# Digitalizador_RPi_Copia_en_conflicto_de_.net
KiCad netlist of a schematic drawn in Altium Designer
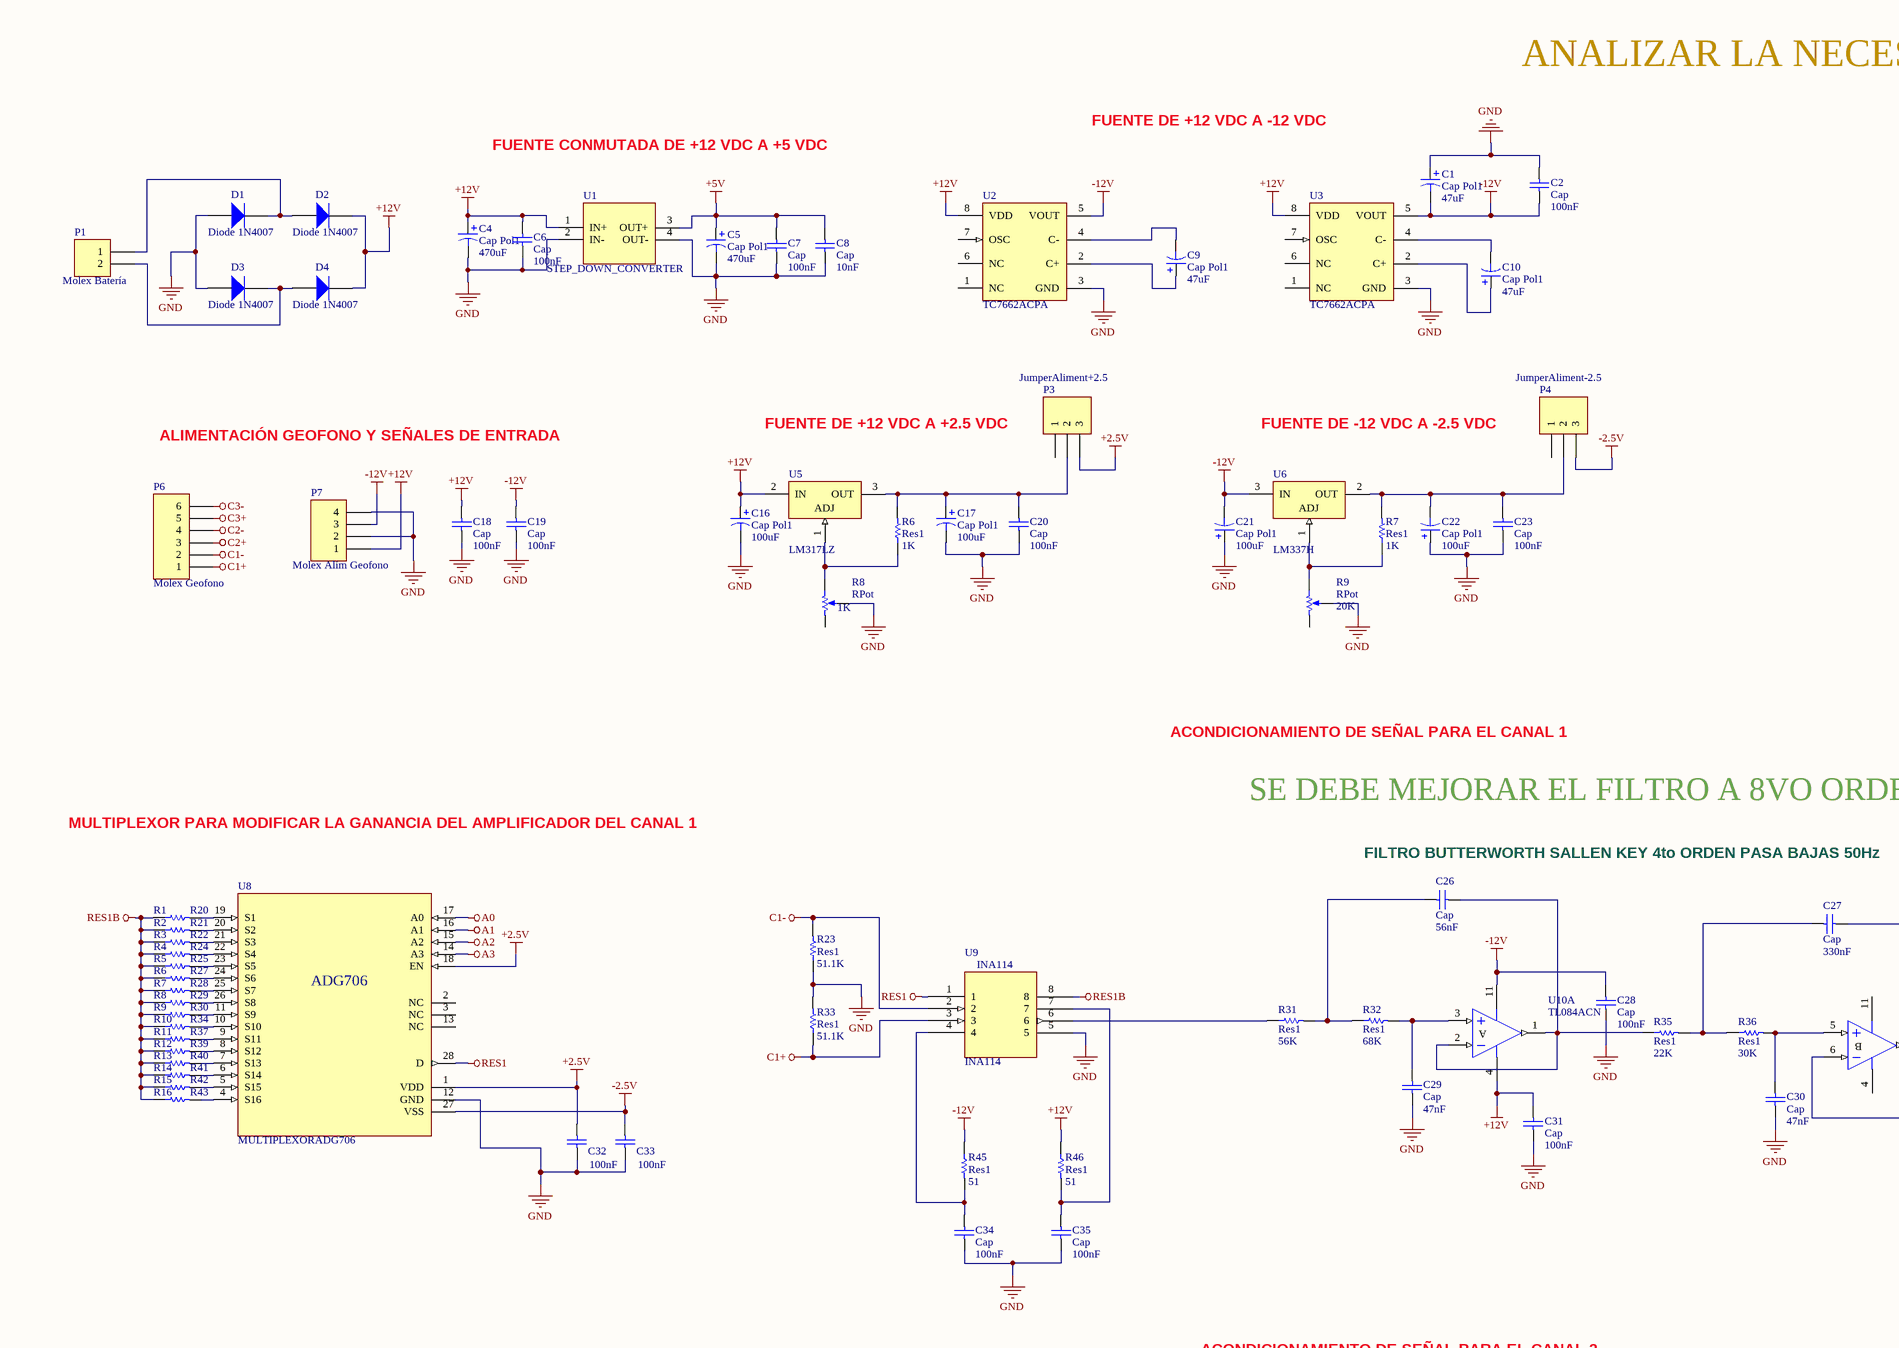
[diagram p0: Digitalizador_RPi (Copia en conflicto de Ivan Palacios 2020-06-25).SchDoc, top left]
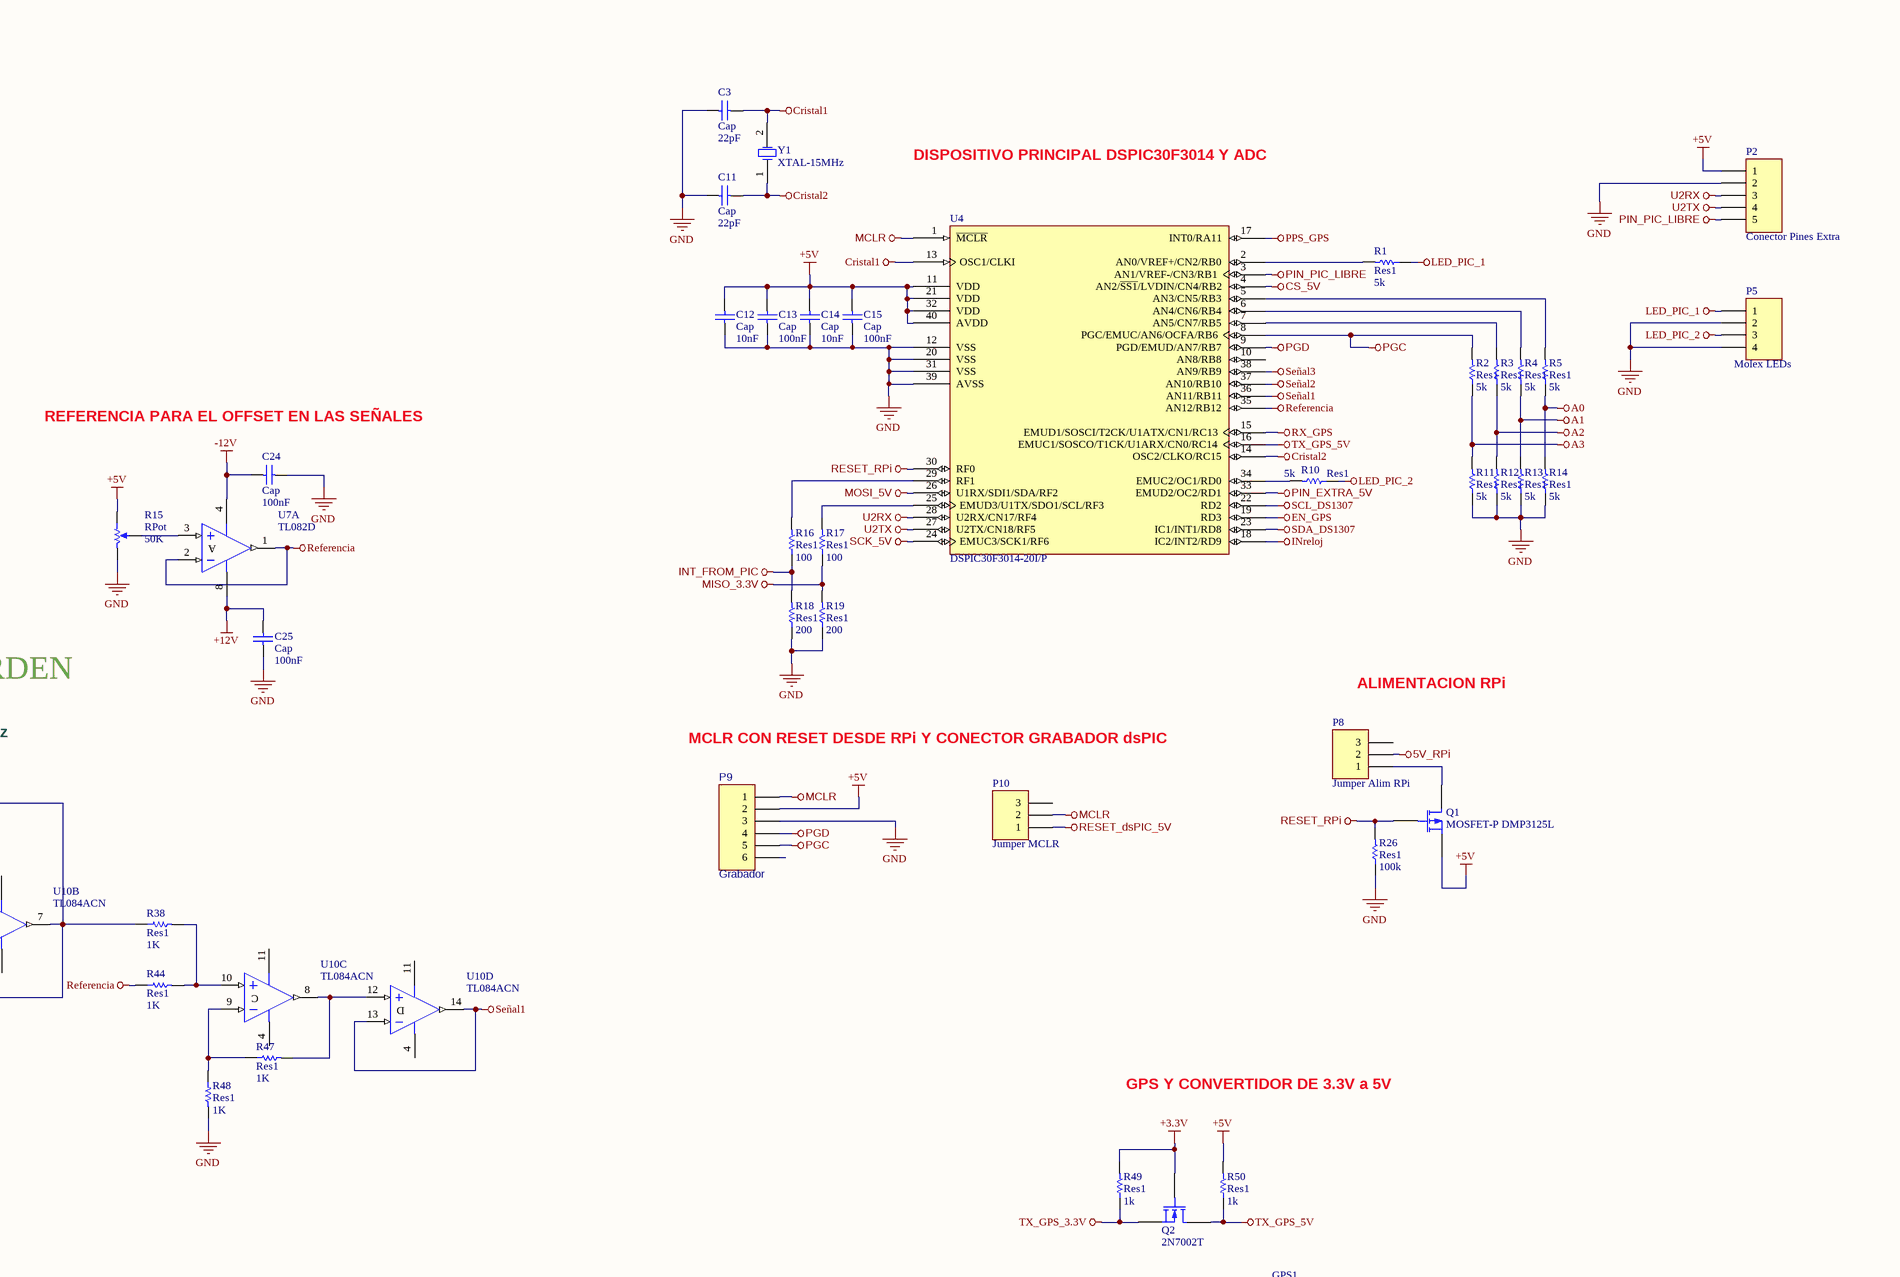
[diagram p1: Digitalizador_RPi (Copia en conflicto de Ivan Palacios 2020-06-25).SchDoc, top right]
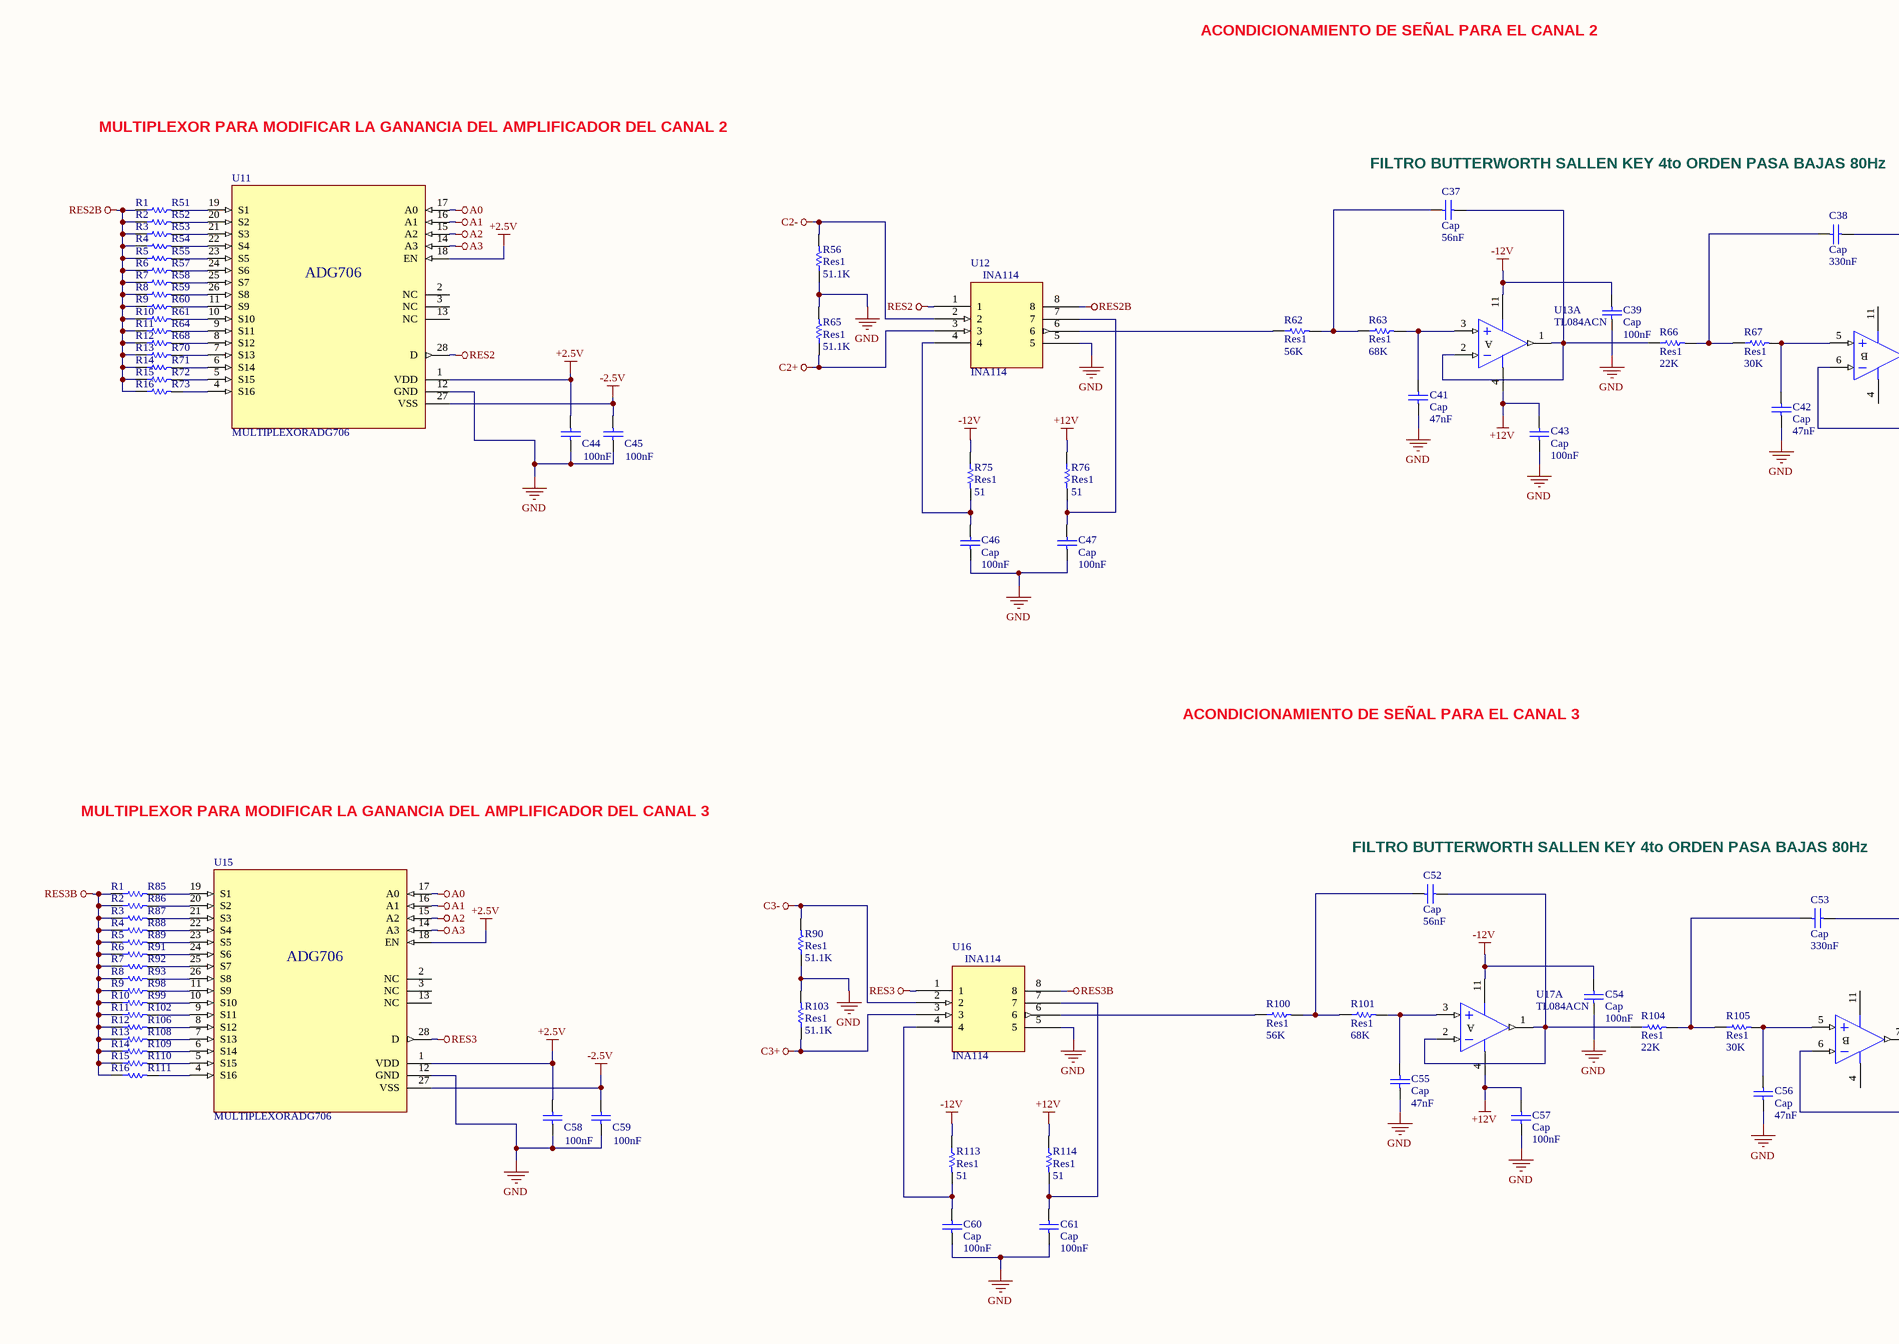
[diagram p2: Digitalizador_RPi (Copia en conflicto de Ivan Palacios 2020-06-25).SchDoc, bottom left]
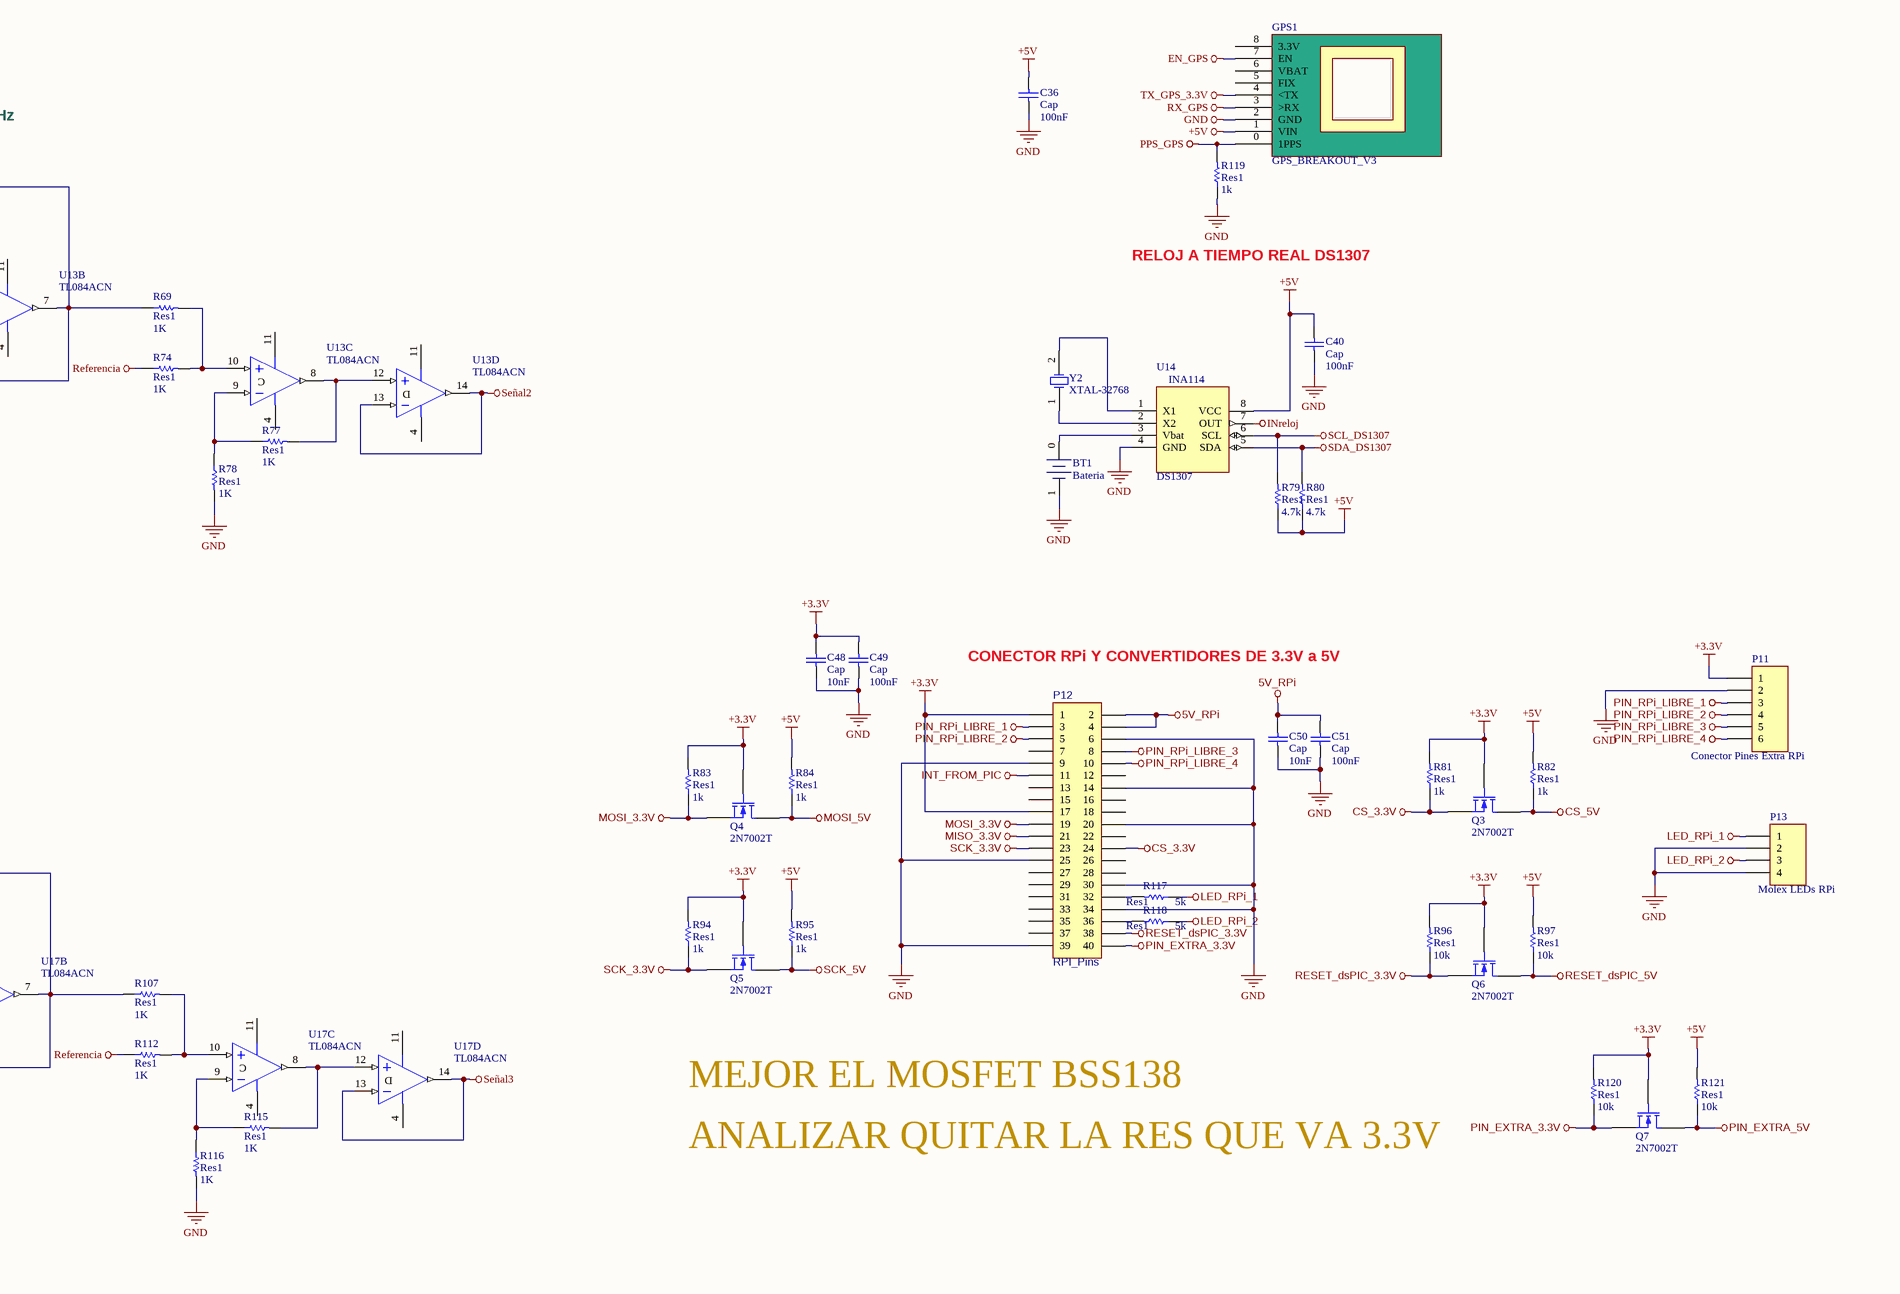
[diagram p3: Digitalizador_RPi (Copia en conflicto de Ivan Palacios 2020-06-25).SchDoc, bottom right]

(export (version "E")
  (design (tool "Eeschema 10.0.6"))
  (components
    (comp (ref "BT1")
      (value "Bateria")
      (footprint "Bateria-DS1307")
      (libsource (lib "Libreria RSA") (part "BateriaDS1307"))
    )
    (comp (ref "C1")
      (value "Cap Pol1")
      (footprint "CAP_5.5MM")
      (description "Polarized Capacitor (Radial)")
      (fields (field (name "ALTIUM_VALUE") "47uF") (field (name "PUBLISHER") "Altium Limited"))
      (libsource (lib "Miscellaneous Devices") (part "Cap Pol1"))
    )
    (comp (ref "C2")
      (value "Cap")
      (footprint "0603")
      (description "Capacitor")
      (fields (field (name "ALTIUM_VALUE") "100nF") (field (name "PUBLISHER") "Altium Limited"))
      (libsource (lib "Miscellaneous Devices") (part "Cap"))
    )
    (comp (ref "C3")
      (value "Cap")
      (footprint "0603")
      (description "Capacitor")
      (fields (field (name "ALTIUM_VALUE") "22pF") (field (name "PUBLISHER") "Altium Limited"))
      (libsource (lib "Miscellaneous Devices") (part "Cap"))
    )
    (comp (ref "C4")
      (value "Cap Pol1")
      (footprint "CAP_8.5mm")
      (description "Polarized Capacitor (Radial)")
      (fields (field (name "ALTIUM_VALUE") "470uF") (field (name "PUBLISHER") "Altium Limited"))
      (libsource (lib "Miscellaneous Devices") (part "Cap Pol1"))
    )
    (comp (ref "C5")
      (value "Cap Pol1")
      (footprint "CAP_8.5mm")
      (description "Polarized Capacitor (Radial)")
      (fields (field (name "ALTIUM_VALUE") "470uF") (field (name "PUBLISHER") "Altium Limited"))
      (libsource (lib "Miscellaneous Devices") (part "Cap Pol1"))
    )
    (comp (ref "C6")
      (value "Cap")
      (footprint "0603")
      (description "Capacitor")
      (fields (field (name "ALTIUM_VALUE") "100nF") (field (name "PUBLISHER") "Altium Limited"))
      (libsource (lib "Miscellaneous Devices") (part "Cap"))
    )
    (comp (ref "C7")
      (value "Cap")
      (footprint "0603")
      (description "Capacitor")
      (fields (field (name "ALTIUM_VALUE") "100nF") (field (name "PUBLISHER") "Altium Limited"))
      (libsource (lib "Miscellaneous Devices") (part "Cap"))
    )
    (comp (ref "C8")
      (value "Cap")
      (footprint "0603")
      (description "Capacitor")
      (fields (field (name "ALTIUM_VALUE") "10nF") (field (name "PUBLISHER") "Altium Limited"))
      (libsource (lib "Miscellaneous Devices") (part "Cap"))
    )
    (comp (ref "C9")
      (value "Cap Pol1")
      (footprint "CAP_5.5MM")
      (description "Polarized Capacitor (Radial)")
      (fields (field (name "ALTIUM_VALUE") "47uF") (field (name "PUBLISHER") "Altium Limited"))
      (libsource (lib "Miscellaneous Devices") (part "Cap Pol1"))
    )
    (comp (ref "C10")
      (value "Cap Pol1")
      (footprint "CAP_5.5MM")
      (description "Polarized Capacitor (Radial)")
      (fields (field (name "ALTIUM_VALUE") "47uF") (field (name "PUBLISHER") "Altium Limited"))
      (libsource (lib "Miscellaneous Devices") (part "Cap Pol1"))
    )
    (comp (ref "C11")
      (value "Cap")
      (footprint "0603")
      (description "Capacitor")
      (fields (field (name "ALTIUM_VALUE") "22pF") (field (name "PUBLISHER") "Altium Limited"))
      (libsource (lib "Miscellaneous Devices") (part "Cap"))
    )
    (comp (ref "C12")
      (value "Cap")
      (footprint "0603")
      (description "Capacitor")
      (fields (field (name "ALTIUM_VALUE") "10nF") (field (name "PUBLISHER") "Altium Limited"))
      (libsource (lib "Miscellaneous Devices") (part "Cap"))
    )
    (comp (ref "C13")
      (value "Cap")
      (footprint "0603")
      (description "Capacitor")
      (fields (field (name "ALTIUM_VALUE") "100nF") (field (name "PUBLISHER") "Altium Limited"))
      (libsource (lib "Miscellaneous Devices") (part "Cap"))
    )
    (comp (ref "C14")
      (value "Cap")
      (footprint "0603")
      (description "Capacitor")
      (fields (field (name "ALTIUM_VALUE") "10nF") (field (name "PUBLISHER") "Altium Limited"))
      (libsource (lib "Miscellaneous Devices") (part "Cap"))
    )
    (comp (ref "C15")
      (value "Cap")
      (footprint "0603")
      (description "Capacitor")
      (fields (field (name "ALTIUM_VALUE") "100nF") (field (name "PUBLISHER") "Altium Limited"))
      (libsource (lib "Miscellaneous Devices") (part "Cap"))
    )
    (comp (ref "C16")
      (value "Cap Pol1")
      (footprint "CAP_5.5MM")
      (description "Polarized Capacitor (Radial)")
      (fields (field (name "ALTIUM_VALUE") "100uF") (field (name "PUBLISHER") "Altium Limited"))
      (libsource (lib "Miscellaneous Devices") (part "Cap Pol1"))
    )
    (comp (ref "C17")
      (value "Cap Pol1")
      (footprint "CAP_5.5MM")
      (description "Polarized Capacitor (Radial)")
      (fields (field (name "ALTIUM_VALUE") "100uF") (field (name "PUBLISHER") "Altium Limited"))
      (libsource (lib "Miscellaneous Devices") (part "Cap Pol1"))
    )
    (comp (ref "C18")
      (value "Cap")
      (footprint "0603")
      (description "Capacitor")
      (fields (field (name "ALTIUM_VALUE") "100nF") (field (name "PUBLISHER") "Altium Limited"))
      (libsource (lib "Miscellaneous Devices") (part "Cap"))
    )
    (comp (ref "C19")
      (value "Cap")
      (footprint "0603")
      (description "Capacitor")
      (fields (field (name "ALTIUM_VALUE") "100nF") (field (name "PUBLISHER") "Altium Limited"))
      (libsource (lib "Miscellaneous Devices") (part "Cap"))
    )
    (comp (ref "C20")
      (value "Cap")
      (footprint "0603")
      (description "Capacitor")
      (fields (field (name "ALTIUM_VALUE") "100nF") (field (name "PUBLISHER") "Altium Limited"))
      (libsource (lib "Miscellaneous Devices") (part "Cap"))
    )
    (comp (ref "C21")
      (value "Cap Pol1")
      (footprint "CAP_5.5MM")
      (description "Polarized Capacitor (Radial)")
      (fields (field (name "ALTIUM_VALUE") "100uF") (field (name "PUBLISHER") "Altium Limited"))
      (libsource (lib "Miscellaneous Devices") (part "Cap Pol1"))
    )
    (comp (ref "C22")
      (value "Cap Pol1")
      (footprint "CAP_5.5MM")
      (description "Polarized Capacitor (Radial)")
      (fields (field (name "ALTIUM_VALUE") "100uF") (field (name "PUBLISHER") "Altium Limited"))
      (libsource (lib "Miscellaneous Devices") (part "Cap Pol1"))
    )
    (comp (ref "C23")
      (value "Cap")
      (footprint "0603")
      (description "Capacitor")
      (fields (field (name "ALTIUM_VALUE") "100nF") (field (name "PUBLISHER") "Altium Limited"))
      (libsource (lib "Miscellaneous Devices") (part "Cap"))
    )
    (comp (ref "C24")
      (value "Cap")
      (footprint "0603")
      (description "Capacitor")
      (fields (field (name "ALTIUM_VALUE") "100nF") (field (name "PUBLISHER") "Altium Limited"))
      (libsource (lib "Miscellaneous Devices") (part "Cap"))
    )
    (comp (ref "C25")
      (value "Cap")
      (footprint "0603")
      (description "Capacitor")
      (fields (field (name "ALTIUM_VALUE") "100nF") (field (name "PUBLISHER") "Altium Limited"))
      (libsource (lib "Miscellaneous Devices") (part "Cap"))
    )
    (comp (ref "C26")
      (value "Cap")
      (footprint "RAD0.2")
      (description "Capacitor")
      (fields (field (name "ALTIUM_VALUE") "56nF") (field (name "PUBLISHER") "Altium Limited"))
      (libsource (lib "Miscellaneous Devices") (part "Cap"))
    )
    (comp (ref "C27")
      (value "Cap")
      (footprint "RAD0.2")
      (description "Capacitor")
      (fields (field (name "ALTIUM_VALUE") "330nF") (field (name "PUBLISHER") "Altium Limited"))
      (libsource (lib "Miscellaneous Devices") (part "Cap"))
    )
    (comp (ref "C28")
      (value "Cap")
      (footprint "0603")
      (description "Capacitor")
      (fields (field (name "ALTIUM_VALUE") "100nF") (field (name "PUBLISHER") "Altium Limited"))
      (libsource (lib "Miscellaneous Devices") (part "Cap"))
    )
    (comp (ref "C29")
      (value "Cap")
      (footprint "RAD0.2")
      (description "Capacitor")
      (fields (field (name "ALTIUM_VALUE") "47nF") (field (name "PUBLISHER") "Altium Limited"))
      (libsource (lib "Miscellaneous Devices") (part "Cap"))
    )
    (comp (ref "C30")
      (value "Cap")
      (footprint "RAD0.2")
      (description "Capacitor")
      (fields (field (name "ALTIUM_VALUE") "47nF") (field (name "PUBLISHER") "Altium Limited"))
      (libsource (lib "Miscellaneous Devices") (part "Cap"))
    )
    (comp (ref "C31")
      (value "Cap")
      (footprint "0603")
      (description "Capacitor")
      (fields (field (name "ALTIUM_VALUE") "100nF") (field (name "PUBLISHER") "Altium Limited"))
      (libsource (lib "Miscellaneous Devices") (part "Cap"))
    )
    (comp (ref "C32")
      (value "100nF")
      (footprint "0603")
      (description "Capacitor ceramico")
      (libsource (lib "Capacitores") (part "Capacitor ceramico"))
    )
    (comp (ref "C33")
      (value "100nF")
      (footprint "0603")
      (description "Capacitor ceramico")
      (libsource (lib "Capacitores") (part "Capacitor ceramico"))
    )
    (comp (ref "C34")
      (value "Cap")
      (footprint "0603")
      (description "Capacitor")
      (fields (field (name "ALTIUM_VALUE") "100nF") (field (name "PUBLISHER") "Altium Limited"))
      (libsource (lib "Miscellaneous Devices") (part "Cap"))
    )
    (comp (ref "C35")
      (value "Cap")
      (footprint "0603")
      (description "Capacitor")
      (fields (field (name "ALTIUM_VALUE") "100nF") (field (name "PUBLISHER") "Altium Limited"))
      (libsource (lib "Miscellaneous Devices") (part "Cap"))
    )
    (comp (ref "C36")
      (value "Cap")
      (footprint "0603")
      (description "Capacitor")
      (fields (field (name "ALTIUM_VALUE") "100nF") (field (name "PUBLISHER") "Altium Limited"))
      (libsource (lib "Miscellaneous Devices") (part "Cap"))
    )
    (comp (ref "C37")
      (value "Cap")
      (footprint "RAD0.2")
      (description "Capacitor")
      (fields (field (name "ALTIUM_VALUE") "56nF") (field (name "PUBLISHER") "Altium Limited"))
      (libsource (lib "Miscellaneous Devices") (part "Cap"))
    )
    (comp (ref "C38")
      (value "Cap")
      (footprint "RAD0.2")
      (description "Capacitor")
      (fields (field (name "ALTIUM_VALUE") "330nF") (field (name "PUBLISHER") "Altium Limited"))
      (libsource (lib "Miscellaneous Devices") (part "Cap"))
    )
    (comp (ref "C39")
      (value "Cap")
      (footprint "0603")
      (description "Capacitor")
      (fields (field (name "ALTIUM_VALUE") "100nF") (field (name "PUBLISHER") "Altium Limited"))
      (libsource (lib "Miscellaneous Devices") (part "Cap"))
    )
    (comp (ref "C40")
      (value "Cap")
      (footprint "0603")
      (description "Capacitor")
      (fields (field (name "ALTIUM_VALUE") "100nF") (field (name "PUBLISHER") "Altium Limited"))
      (libsource (lib "Miscellaneous Devices") (part "Cap"))
    )
    (comp (ref "C41")
      (value "Cap")
      (footprint "RAD0.2")
      (description "Capacitor")
      (fields (field (name "ALTIUM_VALUE") "47nF") (field (name "PUBLISHER") "Altium Limited"))
      (libsource (lib "Miscellaneous Devices") (part "Cap"))
    )
    (comp (ref "C42")
      (value "Cap")
      (footprint "RAD0.2")
      (description "Capacitor")
      (fields (field (name "ALTIUM_VALUE") "47nF") (field (name "PUBLISHER") "Altium Limited"))
      (libsource (lib "Miscellaneous Devices") (part "Cap"))
    )
    (comp (ref "C43")
      (value "Cap")
      (footprint "0603")
      (description "Capacitor")
      (fields (field (name "ALTIUM_VALUE") "100nF") (field (name "PUBLISHER") "Altium Limited"))
      (libsource (lib "Miscellaneous Devices") (part "Cap"))
    )
    (comp (ref "C44")
      (value "100nF")
      (footprint "0603")
      (description "Capacitor ceramico")
      (libsource (lib "Capacitores") (part "Capacitor ceramico"))
    )
    (comp (ref "C45")
      (value "100nF")
      (footprint "0603")
      (description "Capacitor ceramico")
      (libsource (lib "Capacitores") (part "Capacitor ceramico"))
    )
    (comp (ref "C46")
      (value "Cap")
      (footprint "0603")
      (description "Capacitor")
      (fields (field (name "ALTIUM_VALUE") "100nF") (field (name "PUBLISHER") "Altium Limited"))
      (libsource (lib "Miscellaneous Devices") (part "Cap"))
    )
    (comp (ref "C47")
      (value "Cap")
      (footprint "0603")
      (description "Capacitor")
      (fields (field (name "ALTIUM_VALUE") "100nF") (field (name "PUBLISHER") "Altium Limited"))
      (libsource (lib "Miscellaneous Devices") (part "Cap"))
    )
    (comp (ref "C48")
      (value "Cap")
      (footprint "0603")
      (description "Capacitor")
      (fields (field (name "ALTIUM_VALUE") "10nF") (field (name "PUBLISHER") "Altium Limited"))
      (libsource (lib "Miscellaneous Devices") (part "Cap"))
    )
    (comp (ref "C49")
      (value "Cap")
      (footprint "0603")
      (description "Capacitor")
      (fields (field (name "ALTIUM_VALUE") "100nF") (field (name "PUBLISHER") "Altium Limited"))
      (libsource (lib "Miscellaneous Devices") (part "Cap"))
    )
    (comp (ref "C50")
      (value "Cap")
      (footprint "0603")
      (description "Capacitor")
      (fields (field (name "ALTIUM_VALUE") "10nF") (field (name "PUBLISHER") "Altium Limited"))
      (libsource (lib "Miscellaneous Devices") (part "Cap"))
    )
    (comp (ref "C51")
      (value "Cap")
      (footprint "0603")
      (description "Capacitor")
      (fields (field (name "ALTIUM_VALUE") "100nF") (field (name "PUBLISHER") "Altium Limited"))
      (libsource (lib "Miscellaneous Devices") (part "Cap"))
    )
    (comp (ref "C52")
      (value "Cap")
      (footprint "RAD0.2")
      (description "Capacitor")
      (fields (field (name "ALTIUM_VALUE") "56nF") (field (name "PUBLISHER") "Altium Limited"))
      (libsource (lib "Miscellaneous Devices") (part "Cap"))
    )
    (comp (ref "C53")
      (value "Cap")
      (footprint "RAD0.2")
      (description "Capacitor")
      (fields (field (name "ALTIUM_VALUE") "330nF") (field (name "PUBLISHER") "Altium Limited"))
      (libsource (lib "Miscellaneous Devices") (part "Cap"))
    )
    (comp (ref "C54")
      (value "Cap")
      (footprint "0603")
      (description "Capacitor")
      (fields (field (name "ALTIUM_VALUE") "100nF") (field (name "PUBLISHER") "Altium Limited"))
      (libsource (lib "Miscellaneous Devices") (part "Cap"))
    )
    (comp (ref "C55")
      (value "Cap")
      (footprint "RAD0.2")
      (description "Capacitor")
      (fields (field (name "ALTIUM_VALUE") "47nF") (field (name "PUBLISHER") "Altium Limited"))
      (libsource (lib "Miscellaneous Devices") (part "Cap"))
    )
    (comp (ref "C56")
      (value "Cap")
      (footprint "RAD0.2")
      (description "Capacitor")
      (fields (field (name "ALTIUM_VALUE") "47nF") (field (name "PUBLISHER") "Altium Limited"))
      (libsource (lib "Miscellaneous Devices") (part "Cap"))
    )
    (comp (ref "C57")
      (value "Cap")
      (footprint "0603")
      (description "Capacitor")
      (fields (field (name "ALTIUM_VALUE") "100nF") (field (name "PUBLISHER") "Altium Limited"))
      (libsource (lib "Miscellaneous Devices") (part "Cap"))
    )
    (comp (ref "C58")
      (value "100nF")
      (footprint "0603")
      (description "Capacitor ceramico")
      (libsource (lib "Capacitores") (part "Capacitor ceramico"))
    )
    (comp (ref "C59")
      (value "100nF")
      (footprint "0603")
      (description "Capacitor ceramico")
      (libsource (lib "Capacitores") (part "Capacitor ceramico"))
    )
    (comp (ref "C60")
      (value "Cap")
      (footprint "0603")
      (description "Capacitor")
      (fields (field (name "ALTIUM_VALUE") "100nF") (field (name "PUBLISHER") "Altium Limited"))
      (libsource (lib "Miscellaneous Devices") (part "Cap"))
    )
    (comp (ref "C61")
      (value "Cap")
      (footprint "0603")
      (description "Capacitor")
      (fields (field (name "ALTIUM_VALUE") "100nF") (field (name "PUBLISHER") "Altium Limited"))
      (libsource (lib "Miscellaneous Devices") (part "Cap"))
    )
    (comp (ref "D1")
      (value "Diode 1N4007")
      (footprint "DIODE-0.4A")
      (description "1 Amp General Purpose Rectifier")
      (fields (field (name "PUBLISHER") "Altium Limited"))
      (libsource (lib "Miscellaneous Devices") (part "Diode 1N4007"))
    )
    (comp (ref "D2")
      (value "Diode 1N4007")
      (footprint "DIODE-0.4A")
      (description "1 Amp General Purpose Rectifier")
      (fields (field (name "PUBLISHER") "Altium Limited"))
      (libsource (lib "Miscellaneous Devices") (part "Diode 1N4007"))
    )
    (comp (ref "D3")
      (value "Diode 1N4007")
      (footprint "DIODE-0.4A")
      (description "1 Amp General Purpose Rectifier")
      (fields (field (name "PUBLISHER") "Altium Limited"))
      (libsource (lib "Miscellaneous Devices") (part "Diode 1N4007"))
    )
    (comp (ref "D4")
      (value "Diode 1N4007")
      (footprint "DIODE-0.4A")
      (description "1 Amp General Purpose Rectifier")
      (fields (field (name "PUBLISHER") "Altium Limited"))
      (libsource (lib "Miscellaneous Devices") (part "Diode 1N4007"))
    )
    (comp (ref "GPS1")
      (value "GPS_BREAKOUT_V3")
      (footprint "GPS_BREAKOUT_V3")
      (libsource (lib "LibreriaRSA") (part "GPS_BREAKOUT_V3"))
    )
    (comp (ref "P1")
      (value "Molex Batería")
      (footprint "MOLEX-2")
      (description "Header, 2-Pin")
      (fields (field (name "PUBLISHER") "Altium Limited"))
      (libsource (lib "Miscellaneous Connectors") (part "Header 2"))
    )
    (comp (ref "P2")
      (value "Conector Pines Extra")
      (footprint "HDR1X5")
      (description "Header, 5-Pin")
      (fields (field (name "PUBLISHER") "Altium Limited"))
      (libsource (lib "Miscellaneous Connectors") (part "Header 5"))
    )
    (comp (ref "P3")
      (value "JumperAliment+2.5")
      (footprint "SIP-1X3-M")
      (description "Header, 3-Pin")
      (fields (field (name "PUBLISHER") "Altium Limited"))
      (libsource (lib "Miscellaneous Connectors") (part "Header 3"))
    )
    (comp (ref "P4")
      (value "JumperAliment-2.5")
      (footprint "SIP-1X3-M")
      (description "Header, 3-Pin")
      (fields (field (name "PUBLISHER") "Altium Limited"))
      (libsource (lib "Miscellaneous Connectors") (part "Header 3"))
    )
    (comp (ref "P5")
      (value "Molex LEDs")
      (footprint "MOLEX-4")
      (description "Header, 4-Pin")
      (fields (field (name "PUBLISHER") "Altium Limited"))
      (libsource (lib "Miscellaneous Connectors") (part "Header 4"))
    )
    (comp (ref "P6")
      (value "Molex Geofono")
      (footprint "MOLEX-6")
      (description "Header, 6-Pin")
      (fields (field (name "PUBLISHER") "Altium Limited"))
      (libsource (lib "") (part "Header 6_1"))
    )
    (comp (ref "P7")
      (value "Molex Alim Geofono")
      (footprint "MOLEX-4")
      (description "Header, 4-Pin")
      (fields (field (name "PUBLISHER") "Altium Limited"))
      (libsource (lib "") (part "Header 4_1"))
    )
    (comp (ref "P8")
      (value "Jumper Alim RPi")
      (footprint "SIP-1X3-M")
      (description "Header, 3-Pin")
      (fields (field (name "PUBLISHER") "Altium Limited"))
      (libsource (lib "") (part "Header 3_1"))
    )
    (comp (ref "P9")
      (value "Grabador")
      (footprint "HDR1X6")
      (description "Header, 6-Pin")
      (fields (field (name "PUBLISHER") "Altium Limited"))
      (libsource (lib "") (part "Header 6_2"))
    )
    (comp (ref "P10")
      (value "Jumper MCLR")
      (footprint "SIP-1X3-M")
      (description "Header, 3-Pin")
      (fields (field (name "PUBLISHER") "Altium Limited"))
      (libsource (lib "") (part "Header 3_1"))
    )
    (comp (ref "P11")
      (value "Conector Pines Extra RPi")
      (footprint "HDR1X6")
      (description "Header, 6-Pin")
      (fields (field (name "PUBLISHER") "Altium Limited"))
      (libsource (lib "Miscellaneous Connectors") (part "Header 6"))
    )
    (comp (ref "P12")
      (value "RPI_Pins")
      (footprint "SIP-2X20-M")
      (description "Header, 20-Pin, Dual row")
      (fields (field (name "PUBLISHER") "Altium Limited"))
      (libsource (lib "Miscellaneous Connectors") (part "Header 20X2"))
    )
    (comp (ref "P13")
      (value "Molex LEDs RPi")
      (footprint "MOLEX-4")
      (description "Header, 4-Pin")
      (fields (field (name "PUBLISHER") "Altium Limited"))
      (libsource (lib "Miscellaneous Connectors") (part "Header 4"))
    )
    (comp (ref "Q1")
      (value "MOSFET-P DMP3125L")
      (footprint "SOT23-3L")
      (description "P-Channel MOSFET")
      (fields (field (name "PUBLISHER") "Altium Limited"))
      (libsource (lib "Miscellaneous Devices") (part "MOSFET-P"))
    )
    (comp (ref "Q2")
      (value "2N7002T")
      (footprint "SOT523")
      (libsource (lib "Transistores") (part "2N7002T-7-F"))
    )
    (comp (ref "Q3")
      (value "2N7002T")
      (footprint "SOT523")
      (libsource (lib "Transistores") (part "2N7002T-7-F"))
    )
    (comp (ref "Q4")
      (value "2N7002T")
      (footprint "SOT523")
      (libsource (lib "Transistores") (part "2N7002T-7-F"))
    )
    (comp (ref "Q5")
      (value "2N7002T")
      (footprint "SOT523")
      (libsource (lib "Transistores") (part "2N7002T-7-F"))
    )
    (comp (ref "Q6")
      (value "2N7002T")
      (footprint "SOT523")
      (libsource (lib "Transistores") (part "2N7002T-7-F"))
    )
    (comp (ref "Q7")
      (value "2N7002T")
      (footprint "SOT523")
      (libsource (lib "Transistores") (part "2N7002T-7-F"))
    )
    (comp (ref "R1")
      (value "Res1")
      (footprint "0805")
      (description "Resistor")
      (fields (field (name "ALTIUM_VALUE") "5k") (field (name "PUBLISHER") "Altium Limited"))
      (libsource (lib "Resistencias de carbon") (part "Res1"))
    )
    (comp (ref "R2")
      (value "Res1")
      (footprint "0805")
      (description "Resistor")
      (fields (field (name "ALTIUM_VALUE") "5k") (field (name "PUBLISHER") "Altium Limited"))
      (libsource (lib "Resistencias de carbon") (part "Res1"))
    )
    (comp (ref "R3")
      (value "Res1")
      (footprint "0805")
      (description "Resistor")
      (fields (field (name "ALTIUM_VALUE") "5k") (field (name "PUBLISHER") "Altium Limited"))
      (libsource (lib "Resistencias de carbon") (part "Res1"))
    )
    (comp (ref "R4")
      (value "Res1")
      (footprint "0805")
      (description "Resistor")
      (fields (field (name "ALTIUM_VALUE") "5k") (field (name "PUBLISHER") "Altium Limited"))
      (libsource (lib "Resistencias de carbon") (part "Res1"))
    )
    (comp (ref "R5")
      (value "Res1")
      (footprint "0805")
      (description "Resistor")
      (fields (field (name "ALTIUM_VALUE") "5k") (field (name "PUBLISHER") "Altium Limited"))
      (libsource (lib "Resistencias de carbon") (part "Res1"))
    )
    (comp (ref "R6")
      (value "Res1")
      (footprint "0805")
      (description "Resistor")
      (fields (field (name "ALTIUM_VALUE") "1K") (field (name "PUBLISHER") "Altium Limited"))
      (libsource (lib "Resistencias de carbon") (part "Res1"))
    )
    (comp (ref "R7")
      (value "Res1")
      (footprint "0805")
      (description "Resistor")
      (fields (field (name "ALTIUM_VALUE") "1K") (field (name "PUBLISHER") "Altium Limited"))
      (libsource (lib "Resistencias de carbon") (part "Res1"))
    )
    (comp (ref "R8")
      (value "RPot")
      (footprint "VR-5t")
      (description "Potentiometer")
      (fields (field (name "ALTIUM_VALUE") "1K") (field (name "PUBLISHER") "Altium Limited"))
      (libsource (lib "Miscellaneous Devices") (part "RPot"))
    )
    (comp (ref "R9")
      (value "RPot")
      (footprint "VR-5t")
      (description "Potentiometer")
      (fields (field (name "ALTIUM_VALUE") "20K") (field (name "PUBLISHER") "Altium Limited"))
      (libsource (lib "Miscellaneous Devices") (part "RPot"))
    )
    (comp (ref "R10")
      (value "Res1")
      (footprint "0805")
      (description "Resistor")
      (fields (field (name "ALTIUM_VALUE") "5k") (field (name "PUBLISHER") "Altium Limited"))
      (libsource (lib "Resistencias de carbon") (part "Res1"))
    )
    (comp (ref "R11")
      (value "Res1")
      (footprint "0805")
      (description "Resistor")
      (fields (field (name "ALTIUM_VALUE") "5k") (field (name "PUBLISHER") "Altium Limited"))
      (libsource (lib "Resistencias de carbon") (part "Res1"))
    )
    (comp (ref "R12")
      (value "Res1")
      (footprint "0805")
      (description "Resistor")
      (fields (field (name "ALTIUM_VALUE") "5k") (field (name "PUBLISHER") "Altium Limited"))
      (libsource (lib "Resistencias de carbon") (part "Res1"))
    )
    (comp (ref "R13")
      (value "Res1")
      (footprint "0805")
      (description "Resistor")
      (fields (field (name "ALTIUM_VALUE") "5k") (field (name "PUBLISHER") "Altium Limited"))
      (libsource (lib "Resistencias de carbon") (part "Res1"))
    )
    (comp (ref "R14")
      (value "Res1")
      (footprint "0805")
      (description "Resistor")
      (fields (field (name "ALTIUM_VALUE") "5k") (field (name "PUBLISHER") "Altium Limited"))
      (libsource (lib "Resistencias de carbon") (part "Res1"))
    )
    (comp (ref "R15")
      (value "RPot")
      (footprint "VR-5t")
      (description "Potentiometer")
      (fields (field (name "ALTIUM_VALUE") "50K") (field (name "PUBLISHER") "Altium Limited"))
      (libsource (lib "Miscellaneous Devices") (part "RPot"))
    )
    (comp (ref "R16")
      (value "Res1")
      (footprint "0805")
      (description "Resistor")
      (fields (field (name "ALTIUM_VALUE") "100") (field (name "PUBLISHER") "Altium Limited"))
      (libsource (lib "Resistencias de carbon") (part "Res1"))
    )
    (comp (ref "R17")
      (value "Res1")
      (footprint "0805")
      (description "Resistor")
      (fields (field (name "ALTIUM_VALUE") "100") (field (name "PUBLISHER") "Altium Limited"))
      (libsource (lib "Resistencias de carbon") (part "Res1"))
    )
    (comp (ref "R18")
      (value "Res1")
      (footprint "0805")
      (description "Resistor")
      (fields (field (name "ALTIUM_VALUE") "200") (field (name "PUBLISHER") "Altium Limited"))
      (libsource (lib "Resistencias de carbon") (part "Res1"))
    )
    (comp (ref "R19")
      (value "Res1")
      (footprint "0805")
      (description "Resistor")
      (fields (field (name "ALTIUM_VALUE") "200") (field (name "PUBLISHER") "Altium Limited"))
      (libsource (lib "Resistencias de carbon") (part "Res1"))
    )
    (comp (ref "R20")
      (value "R1")
      (footprint "0805")
      (description "Resistor")
      (fields (field (name "PUBLISHER") "Altium Limited"))
      (libsource (lib "Resistencias de carbon") (part "Res1"))
    )
    (comp (ref "R21")
      (value "R2")
      (footprint "0805")
      (description "Resistor")
      (fields (field (name "PUBLISHER") "Altium Limited"))
      (libsource (lib "Resistencias de carbon") (part "Res1"))
    )
    (comp (ref "R22")
      (value "R3")
      (footprint "0805")
      (description "Resistor")
      (fields (field (name "PUBLISHER") "Altium Limited"))
      (libsource (lib "Resistencias de carbon") (part "Res1"))
    )
    (comp (ref "R23")
      (value "Res1")
      (footprint "0805")
      (description "Resistor")
      (fields (field (name "ALTIUM_VALUE") "51.1K") (field (name "PUBLISHER") "Altium Limited"))
      (libsource (lib "Resistencias de carbon") (part "Res1"))
    )
    (comp (ref "R24")
      (value "R4")
      (footprint "0805")
      (description "Resistor")
      (fields (field (name "PUBLISHER") "Altium Limited"))
      (libsource (lib "Resistencias de carbon") (part "Res1"))
    )
    (comp (ref "R25")
      (value "R5")
      (footprint "0805")
      (description "Resistor")
      (fields (field (name "PUBLISHER") "Altium Limited"))
      (libsource (lib "Resistencias de carbon") (part "Res1"))
    )
    (comp (ref "R26")
      (value "Res1")
      (footprint "0805")
      (description "Resistor")
      (fields (field (name "ALTIUM_VALUE") "100k") (field (name "PUBLISHER") "Altium Limited"))
      (libsource (lib "Resistencias de carbon") (part "Res1"))
    )
    (comp (ref "R27")
      (value "R6")
      (footprint "0805")
      (description "Resistor")
      (fields (field (name "PUBLISHER") "Altium Limited"))
      (libsource (lib "Resistencias de carbon") (part "Res1"))
    )
    (comp (ref "R28")
      (value "R7")
      (footprint "0805")
      (description "Resistor")
      (fields (field (name "PUBLISHER") "Altium Limited"))
      (libsource (lib "Resistencias de carbon") (part "Res1"))
    )
    (comp (ref "R29")
      (value "R8")
      (footprint "0805")
      (description "Resistor")
      (fields (field (name "PUBLISHER") "Altium Limited"))
      (libsource (lib "Resistencias de carbon") (part "Res1"))
    )
    (comp (ref "R30")
      (value "R9")
      (footprint "0805")
      (description "Resistor")
      (fields (field (name "PUBLISHER") "Altium Limited"))
      (libsource (lib "Resistencias de carbon") (part "Res1"))
    )
    (comp (ref "R31")
      (value "Res1")
      (footprint "0805")
      (description "Resistor")
      (fields (field (name "ALTIUM_VALUE") "56K") (field (name "PUBLISHER") "Altium Limited"))
      (libsource (lib "Resistencias de carbon") (part "Res1"))
    )
    (comp (ref "R32")
      (value "Res1")
      (footprint "0805")
      (description "Resistor")
      (fields (field (name "ALTIUM_VALUE") "68K") (field (name "PUBLISHER") "Altium Limited"))
      (libsource (lib "Resistencias de carbon") (part "Res1"))
    )
    (comp (ref "R33")
      (value "Res1")
      (footprint "0805")
      (description "Resistor")
      (fields (field (name "ALTIUM_VALUE") "51.1K") (field (name "PUBLISHER") "Altium Limited"))
      (libsource (lib "Resistencias de carbon") (part "Res1"))
    )
    (comp (ref "R34")
      (value "R10")
      (footprint "0805")
      (description "Resistor")
      (fields (field (name "PUBLISHER") "Altium Limited"))
      (libsource (lib "Resistencias de carbon") (part "Res1"))
    )
    (comp (ref "R35")
      (value "Res1")
      (footprint "0805")
      (description "Resistor")
      (fields (field (name "ALTIUM_VALUE") "22K") (field (name "PUBLISHER") "Altium Limited"))
      (libsource (lib "Resistencias de carbon") (part "Res1"))
    )
    (comp (ref "R36")
      (value "Res1")
      (footprint "0805")
      (description "Resistor")
      (fields (field (name "ALTIUM_VALUE") "30K") (field (name "PUBLISHER") "Altium Limited"))
      (libsource (lib "Resistencias de carbon") (part "Res1"))
    )
    (comp (ref "R37")
      (value "R11")
      (footprint "0805")
      (description "Resistor")
      (fields (field (name "PUBLISHER") "Altium Limited"))
      (libsource (lib "Resistencias de carbon") (part "Res1"))
    )
    (comp (ref "R38")
      (value "Res1")
      (footprint "0805")
      (description "Resistor")
      (fields (field (name "ALTIUM_VALUE") "1K") (field (name "PUBLISHER") "Altium Limited"))
      (libsource (lib "Resistencias de carbon") (part "Res1"))
    )
    (comp (ref "R39")
      (value "R12")
      (footprint "0805")
      (description "Resistor")
      (fields (field (name "PUBLISHER") "Altium Limited"))
      (libsource (lib "Resistencias de carbon") (part "Res1"))
    )
    (comp (ref "R40")
      (value "R13")
      (footprint "0805")
      (description "Resistor")
      (fields (field (name "PUBLISHER") "Altium Limited"))
      (libsource (lib "Resistencias de carbon") (part "Res1"))
    )
    (comp (ref "R41")
      (value "R14")
      (footprint "0805")
      (description "Resistor")
      (fields (field (name "PUBLISHER") "Altium Limited"))
      (libsource (lib "Resistencias de carbon") (part "Res1"))
    )
    (comp (ref "R42")
      (value "R15")
      (footprint "0805")
      (description "Resistor")
      (fields (field (name "PUBLISHER") "Altium Limited"))
      (libsource (lib "Resistencias de carbon") (part "Res1"))
    )
    (comp (ref "R43")
      (value "R16")
      (footprint "0805")
      (description "Resistor")
      (fields (field (name "PUBLISHER") "Altium Limited"))
      (libsource (lib "Resistencias de carbon") (part "Res1"))
    )
    (comp (ref "R44")
      (value "Res1")
      (footprint "0805")
      (description "Resistor")
      (fields (field (name "ALTIUM_VALUE") "1K") (field (name "PUBLISHER") "Altium Limited"))
      (libsource (lib "Resistencias de carbon") (part "Res1"))
    )
    (comp (ref "R45")
      (value "Res1")
      (footprint "0805")
      (description "Resistor")
      (fields (field (name "ALTIUM_VALUE") "51") (field (name "PUBLISHER") "Altium Limited"))
      (libsource (lib "Resistencias de carbon") (part "Res1"))
    )
    (comp (ref "R46")
      (value "Res1")
      (footprint "0805")
      (description "Resistor")
      (fields (field (name "ALTIUM_VALUE") "51") (field (name "PUBLISHER") "Altium Limited"))
      (libsource (lib "Resistencias de carbon") (part "Res1"))
    )
    (comp (ref "R47")
      (value "Res1")
      (footprint "0805")
      (description "Resistor")
      (fields (field (name "ALTIUM_VALUE") "1K") (field (name "PUBLISHER") "Altium Limited"))
      (libsource (lib "Resistencias de carbon") (part "Res1"))
    )
    (comp (ref "R48")
      (value "Res1")
      (footprint "0805")
      (description "Resistor")
      (fields (field (name "ALTIUM_VALUE") "1K") (field (name "PUBLISHER") "Altium Limited"))
      (libsource (lib "Resistencias de carbon") (part "Res1"))
    )
    (comp (ref "R49")
      (value "Res1")
      (footprint "0805")
      (description "Resistor")
      (fields (field (name "ALTIUM_VALUE") "1k") (field (name "PUBLISHER") "Altium Limited"))
      (libsource (lib "Resistencias de carbon") (part "Res1"))
    )
    (comp (ref "R50")
      (value "Res1")
      (footprint "0805")
      (description "Resistor")
      (fields (field (name "ALTIUM_VALUE") "1k") (field (name "PUBLISHER") "Altium Limited"))
      (libsource (lib "Resistencias de carbon") (part "Res1"))
    )
    (comp (ref "R51")
      (value "R1")
      (footprint "0805")
      (description "Resistor")
      (fields (field (name "PUBLISHER") "Altium Limited"))
      (libsource (lib "Resistencias de carbon") (part "Res1"))
    )
    (comp (ref "R52")
      (value "R2")
      (footprint "0805")
      (description "Resistor")
      (fields (field (name "PUBLISHER") "Altium Limited"))
      (libsource (lib "Resistencias de carbon") (part "Res1"))
    )
    (comp (ref "R53")
      (value "R3")
      (footprint "0805")
      (description "Resistor")
      (fields (field (name "PUBLISHER") "Altium Limited"))
      (libsource (lib "Resistencias de carbon") (part "Res1"))
    )
    (comp (ref "R54")
      (value "R4")
      (footprint "0805")
      (description "Resistor")
      (fields (field (name "PUBLISHER") "Altium Limited"))
      (libsource (lib "Resistencias de carbon") (part "Res1"))
    )
    (comp (ref "R55")
      (value "R5")
      (footprint "0805")
      (description "Resistor")
      (fields (field (name "PUBLISHER") "Altium Limited"))
      (libsource (lib "Resistencias de carbon") (part "Res1"))
    )
    (comp (ref "R56")
      (value "Res1")
      (footprint "0805")
      (description "Resistor")
      (fields (field (name "ALTIUM_VALUE") "51.1K") (field (name "PUBLISHER") "Altium Limited"))
      (libsource (lib "Resistencias de carbon") (part "Res1"))
    )
    (comp (ref "R57")
      (value "R6")
      (footprint "0805")
      (description "Resistor")
      (fields (field (name "PUBLISHER") "Altium Limited"))
      (libsource (lib "Resistencias de carbon") (part "Res1"))
    )
    (comp (ref "R58")
      (value "R7")
      (footprint "0805")
      (description "Resistor")
      (fields (field (name "PUBLISHER") "Altium Limited"))
      (libsource (lib "Resistencias de carbon") (part "Res1"))
    )
    (comp (ref "R59")
      (value "R8")
      (footprint "0805")
      (description "Resistor")
      (fields (field (name "PUBLISHER") "Altium Limited"))
      (libsource (lib "Resistencias de carbon") (part "Res1"))
    )
    (comp (ref "R60")
      (value "R9")
      (footprint "0805")
      (description "Resistor")
      (fields (field (name "PUBLISHER") "Altium Limited"))
      (libsource (lib "Resistencias de carbon") (part "Res1"))
    )
    (comp (ref "R61")
      (value "R10")
      (footprint "0805")
      (description "Resistor")
      (fields (field (name "PUBLISHER") "Altium Limited"))
      (libsource (lib "Resistencias de carbon") (part "Res1"))
    )
    (comp (ref "R62")
      (value "Res1")
      (footprint "0805")
      (description "Resistor")
      (fields (field (name "ALTIUM_VALUE") "56K") (field (name "PUBLISHER") "Altium Limited"))
      (libsource (lib "Resistencias de carbon") (part "Res1"))
    )
    (comp (ref "R63")
      (value "Res1")
      (footprint "0805")
      (description "Resistor")
      (fields (field (name "ALTIUM_VALUE") "68K") (field (name "PUBLISHER") "Altium Limited"))
      (libsource (lib "Resistencias de carbon") (part "Res1"))
    )
    (comp (ref "R64")
      (value "R11")
      (footprint "0805")
      (description "Resistor")
      (fields (field (name "PUBLISHER") "Altium Limited"))
      (libsource (lib "Resistencias de carbon") (part "Res1"))
    )
    (comp (ref "R65")
      (value "Res1")
      (footprint "0805")
      (description "Resistor")
      (fields (field (name "ALTIUM_VALUE") "51.1K") (field (name "PUBLISHER") "Altium Limited"))
      (libsource (lib "Resistencias de carbon") (part "Res1"))
    )
    (comp (ref "R66")
      (value "Res1")
      (footprint "0805")
      (description "Resistor")
      (fields (field (name "ALTIUM_VALUE") "22K") (field (name "PUBLISHER") "Altium Limited"))
      (libsource (lib "Resistencias de carbon") (part "Res1"))
    )
    (comp (ref "R67")
      (value "Res1")
      (footprint "0805")
      (description "Resistor")
      (fields (field (name "ALTIUM_VALUE") "30K") (field (name "PUBLISHER") "Altium Limited"))
      (libsource (lib "Resistencias de carbon") (part "Res1"))
    )
    (comp (ref "R68")
      (value "R12")
      (footprint "0805")
      (description "Resistor")
      (fields (field (name "PUBLISHER") "Altium Limited"))
      (libsource (lib "Resistencias de carbon") (part "Res1"))
    )
    (comp (ref "R69")
      (value "Res1")
      (footprint "0805")
      (description "Resistor")
      (fields (field (name "ALTIUM_VALUE") "1K") (field (name "PUBLISHER") "Altium Limited"))
      (libsource (lib "Resistencias de carbon") (part "Res1"))
    )
    (comp (ref "R70")
      (value "R13")
      (footprint "0805")
      (description "Resistor")
      (fields (field (name "PUBLISHER") "Altium Limited"))
      (libsource (lib "Resistencias de carbon") (part "Res1"))
    )
    (comp (ref "R71")
      (value "R14")
      (footprint "0805")
      (description "Resistor")
      (fields (field (name "PUBLISHER") "Altium Limited"))
      (libsource (lib "Resistencias de carbon") (part "Res1"))
    )
    (comp (ref "R72")
      (value "R15")
      (footprint "0805")
      (description "Resistor")
      (fields (field (name "PUBLISHER") "Altium Limited"))
      (libsource (lib "Resistencias de carbon") (part "Res1"))
    )
    (comp (ref "R73")
      (value "R16")
      (footprint "0805")
      (description "Resistor")
      (fields (field (name "PUBLISHER") "Altium Limited"))
      (libsource (lib "Resistencias de carbon") (part "Res1"))
    )
    (comp (ref "R74")
      (value "Res1")
      (footprint "0805")
      (description "Resistor")
      (fields (field (name "ALTIUM_VALUE") "1K") (field (name "PUBLISHER") "Altium Limited"))
      (libsource (lib "Resistencias de carbon") (part "Res1"))
    )
    (comp (ref "R75")
      (value "Res1")
      (footprint "0805")
      (description "Resistor")
      (fields (field (name "ALTIUM_VALUE") "51") (field (name "PUBLISHER") "Altium Limited"))
      (libsource (lib "Resistencias de carbon") (part "Res1"))
    )
    (comp (ref "R76")
      (value "Res1")
      (footprint "0805")
      (description "Resistor")
      (fields (field (name "ALTIUM_VALUE") "51") (field (name "PUBLISHER") "Altium Limited"))
      (libsource (lib "Resistencias de carbon") (part "Res1"))
    )
    (comp (ref "R77")
      (value "Res1")
      (footprint "0805")
      (description "Resistor")
      (fields (field (name "ALTIUM_VALUE") "1K") (field (name "PUBLISHER") "Altium Limited"))
      (libsource (lib "Resistencias de carbon") (part "Res1"))
    )
    (comp (ref "R78")
      (value "Res1")
      (footprint "0805")
      (description "Resistor")
      (fields (field (name "ALTIUM_VALUE") "1K") (field (name "PUBLISHER") "Altium Limited"))
      (libsource (lib "Resistencias de carbon") (part "Res1"))
    )
    (comp (ref "R79")
      (value "Res1")
      (footprint "0805")
      (description "Resistor")
      (fields (field (name "ALTIUM_VALUE") "4.7k") (field (name "PUBLISHER") "Altium Limited"))
      (libsource (lib "Resistencias de carbon") (part "Res1"))
    )
    (comp (ref "R80")
      (value "Res1")
      (footprint "0805")
      (description "Resistor")
      (fields (field (name "ALTIUM_VALUE") "4.7k") (field (name "PUBLISHER") "Altium Limited"))
      (libsource (lib "Resistencias de carbon") (part "Res1"))
    )
    (comp (ref "R81")
      (value "Res1")
      (footprint "0805")
      (description "Resistor")
      (fields (field (name "ALTIUM_VALUE") "1k") (field (name "PUBLISHER") "Altium Limited"))
      (libsource (lib "Resistencias de carbon") (part "Res1"))
    )
    (comp (ref "R82")
      (value "Res1")
      (footprint "0805")
      (description "Resistor")
      (fields (field (name "ALTIUM_VALUE") "1k") (field (name "PUBLISHER") "Altium Limited"))
      (libsource (lib "Resistencias de carbon") (part "Res1"))
    )
    (comp (ref "R83")
      (value "Res1")
      (footprint "0805")
      (description "Resistor")
      (fields (field (name "ALTIUM_VALUE") "1k") (field (name "PUBLISHER") "Altium Limited"))
      (libsource (lib "Resistencias de carbon") (part "Res1"))
    )
    (comp (ref "R84")
      (value "Res1")
      (footprint "0805")
      (description "Resistor")
      (fields (field (name "ALTIUM_VALUE") "1k") (field (name "PUBLISHER") "Altium Limited"))
      (libsource (lib "Resistencias de carbon") (part "Res1"))
    )
    (comp (ref "R85")
      (value "R1")
      (footprint "0805")
      (description "Resistor")
      (fields (field (name "PUBLISHER") "Altium Limited"))
      (libsource (lib "Resistencias de carbon") (part "Res1"))
    )
    (comp (ref "R86")
      (value "R2")
      (footprint "0805")
      (description "Resistor")
      (fields (field (name "PUBLISHER") "Altium Limited"))
      (libsource (lib "Resistencias de carbon") (part "Res1"))
    )
    (comp (ref "R87")
      (value "R3")
      (footprint "0805")
      (description "Resistor")
      (fields (field (name "PUBLISHER") "Altium Limited"))
      (libsource (lib "Resistencias de carbon") (part "Res1"))
    )
    (comp (ref "R88")
      (value "R4")
      (footprint "0805")
      (description "Resistor")
      (fields (field (name "PUBLISHER") "Altium Limited"))
      (libsource (lib "Resistencias de carbon") (part "Res1"))
    )
    (comp (ref "R89")
      (value "R5")
      (footprint "0805")
      (description "Resistor")
      (fields (field (name "PUBLISHER") "Altium Limited"))
      (libsource (lib "Resistencias de carbon") (part "Res1"))
    )
    (comp (ref "R90")
      (value "Res1")
      (footprint "0805")
      (description "Resistor")
      (fields (field (name "ALTIUM_VALUE") "51.1K") (field (name "PUBLISHER") "Altium Limited"))
      (libsource (lib "Resistencias de carbon") (part "Res1"))
    )
    (comp (ref "R91")
      (value "R6")
      (footprint "0805")
      (description "Resistor")
      (fields (field (name "PUBLISHER") "Altium Limited"))
      (libsource (lib "Resistencias de carbon") (part "Res1"))
    )
    (comp (ref "R92")
      (value "R7")
      (footprint "0805")
      (description "Resistor")
      (fields (field (name "PUBLISHER") "Altium Limited"))
      (libsource (lib "Resistencias de carbon") (part "Res1"))
    )
    (comp (ref "R93")
      (value "R8")
      (footprint "0805")
      (description "Resistor")
      (fields (field (name "PUBLISHER") "Altium Limited"))
      (libsource (lib "Resistencias de carbon") (part "Res1"))
    )
    (comp (ref "R94")
      (value "Res1")
      (footprint "0805")
      (description "Resistor")
      (fields (field (name "ALTIUM_VALUE") "1k") (field (name "PUBLISHER") "Altium Limited"))
      (libsource (lib "Resistencias de carbon") (part "Res1"))
    )
    (comp (ref "R95")
      (value "Res1")
      (footprint "0805")
      (description "Resistor")
      (fields (field (name "ALTIUM_VALUE") "1k") (field (name "PUBLISHER") "Altium Limited"))
      (libsource (lib "Resistencias de carbon") (part "Res1"))
    )
    (comp (ref "R96")
      (value "Res1")
      (footprint "0805")
      (description "Resistor")
      (fields (field (name "ALTIUM_VALUE") "10k") (field (name "PUBLISHER") "Altium Limited"))
      (libsource (lib "Resistencias de carbon") (part "Res1"))
    )
    (comp (ref "R97")
      (value "Res1")
      (footprint "0805")
      (description "Resistor")
      (fields (field (name "ALTIUM_VALUE") "10k") (field (name "PUBLISHER") "Altium Limited"))
      (libsource (lib "Resistencias de carbon") (part "Res1"))
    )
    (comp (ref "R98")
      (value "R9")
      (footprint "0805")
      (description "Resistor")
      (fields (field (name "PUBLISHER") "Altium Limited"))
      (libsource (lib "Resistencias de carbon") (part "Res1"))
    )
    (comp (ref "R99")
      (value "R10")
      (footprint "0805")
      (description "Resistor")
      (fields (field (name "PUBLISHER") "Altium Limited"))
      (libsource (lib "Resistencias de carbon") (part "Res1"))
    )
    (comp (ref "R100")
      (value "Res1")
      (footprint "0805")
      (description "Resistor")
      (fields (field (name "ALTIUM_VALUE") "56K") (field (name "PUBLISHER") "Altium Limited"))
      (libsource (lib "Resistencias de carbon") (part "Res1"))
    )
    (comp (ref "R101")
      (value "Res1")
      (footprint "0805")
      (description "Resistor")
      (fields (field (name "ALTIUM_VALUE") "68K") (field (name "PUBLISHER") "Altium Limited"))
      (libsource (lib "Resistencias de carbon") (part "Res1"))
    )
    (comp (ref "R102")
      (value "R11")
      (footprint "0805")
      (description "Resistor")
      (fields (field (name "PUBLISHER") "Altium Limited"))
      (libsource (lib "Resistencias de carbon") (part "Res1"))
    )
    (comp (ref "R103")
      (value "Res1")
      (footprint "0805")
      (description "Resistor")
      (fields (field (name "ALTIUM_VALUE") "51.1K") (field (name "PUBLISHER") "Altium Limited"))
      (libsource (lib "Resistencias de carbon") (part "Res1"))
    )
    (comp (ref "R104")
      (value "Res1")
      (footprint "0805")
      (description "Resistor")
      (fields (field (name "ALTIUM_VALUE") "22K") (field (name "PUBLISHER") "Altium Limited"))
      (libsource (lib "Resistencias de carbon") (part "Res1"))
    )
    (comp (ref "R105")
      (value "Res1")
      (footprint "0805")
      (description "Resistor")
      (fields (field (name "ALTIUM_VALUE") "30K") (field (name "PUBLISHER") "Altium Limited"))
      (libsource (lib "Resistencias de carbon") (part "Res1"))
    )
    (comp (ref "R106")
      (value "R12")
      (footprint "0805")
      (description "Resistor")
      (fields (field (name "PUBLISHER") "Altium Limited"))
      (libsource (lib "Resistencias de carbon") (part "Res1"))
    )
    (comp (ref "R107")
      (value "Res1")
      (footprint "0805")
      (description "Resistor")
      (fields (field (name "ALTIUM_VALUE") "1K") (field (name "PUBLISHER") "Altium Limited"))
      (libsource (lib "Resistencias de carbon") (part "Res1"))
    )
    (comp (ref "R108")
      (value "R13")
      (footprint "0805")
      (description "Resistor")
      (fields (field (name "PUBLISHER") "Altium Limited"))
      (libsource (lib "Resistencias de carbon") (part "Res1"))
    )
    (comp (ref "R109")
      (value "R14")
      (footprint "0805")
      (description "Resistor")
      (fields (field (name "PUBLISHER") "Altium Limited"))
      (libsource (lib "Resistencias de carbon") (part "Res1"))
    )
    (comp (ref "R110")
      (value "R15")
      (footprint "0805")
      (description "Resistor")
      (fields (field (name "PUBLISHER") "Altium Limited"))
      (libsource (lib "Resistencias de carbon") (part "Res1"))
    )
    (comp (ref "R111")
      (value "R16")
      (footprint "0805")
      (description "Resistor")
      (fields (field (name "PUBLISHER") "Altium Limited"))
      (libsource (lib "Resistencias de carbon") (part "Res1"))
    )
    (comp (ref "R112")
      (value "Res1")
      (footprint "0805")
      (description "Resistor")
      (fields (field (name "ALTIUM_VALUE") "1K") (field (name "PUBLISHER") "Altium Limited"))
      (libsource (lib "Resistencias de carbon") (part "Res1"))
    )
    (comp (ref "R113")
      (value "Res1")
      (footprint "0805")
      (description "Resistor")
      (fields (field (name "ALTIUM_VALUE") "51") (field (name "PUBLISHER") "Altium Limited"))
      (libsource (lib "Resistencias de carbon") (part "Res1"))
    )
    (comp (ref "R114")
      (value "Res1")
      (footprint "0805")
      (description "Resistor")
      (fields (field (name "ALTIUM_VALUE") "51") (field (name "PUBLISHER") "Altium Limited"))
      (libsource (lib "Resistencias de carbon") (part "Res1"))
    )
    (comp (ref "R115")
      (value "Res1")
      (footprint "0805")
      (description "Resistor")
      (fields (field (name "ALTIUM_VALUE") "1K") (field (name "PUBLISHER") "Altium Limited"))
      (libsource (lib "Resistencias de carbon") (part "Res1"))
    )
    (comp (ref "R116")
      (value "Res1")
      (footprint "0805")
      (description "Resistor")
      (fields (field (name "ALTIUM_VALUE") "1K") (field (name "PUBLISHER") "Altium Limited"))
      (libsource (lib "Resistencias de carbon") (part "Res1"))
    )
    (comp (ref "R117")
      (value "Res1")
      (footprint "0805")
      (description "Resistor")
      (fields (field (name "ALTIUM_VALUE") "5k") (field (name "PUBLISHER") "Altium Limited"))
      (libsource (lib "Resistencias de carbon") (part "Res1"))
    )
    (comp (ref "R118")
      (value "Res1")
      (footprint "0805")
      (description "Resistor")
      (fields (field (name "ALTIUM_VALUE") "5k") (field (name "PUBLISHER") "Altium Limited"))
      (libsource (lib "Resistencias de carbon") (part "Res1"))
    )
    (comp (ref "R119")
      (value "Res1")
      (footprint "0805")
      (description "Resistor")
      (fields (field (name "ALTIUM_VALUE") "1k") (field (name "PUBLISHER") "Altium Limited"))
      (libsource (lib "Resistencias de carbon") (part "Res1"))
    )
    (comp (ref "R120")
      (value "Res1")
      (footprint "0805")
      (description "Resistor")
      (fields (field (name "ALTIUM_VALUE") "10k") (field (name "PUBLISHER") "Altium Limited"))
      (libsource (lib "Resistencias de carbon") (part "Res1"))
    )
    (comp (ref "R121")
      (value "Res1")
      (footprint "0805")
      (description "Resistor")
      (fields (field (name "ALTIUM_VALUE") "10k") (field (name "PUBLISHER") "Altium Limited"))
      (libsource (lib "Resistencias de carbon") (part "Res1"))
    )
    (comp (ref "U1")
      (value "STEP_DOWN_CONVERTER")
      (footprint "STEP_DOWN_CONVERTER")
      (libsource (lib "LibreriaRSA") (part "STEP_DOWN_CONVERTER"))
    )
    (comp (ref "U2")
      (value "TC7662ACPA")
      (footprint "DIP-8")
      (description "Super Charge Pump DC-to-DC Voltage Converter, 12kHz, 8-Pin PDIP, Commercial Temperature")
      (fields (field (name "PUBLISHER") "Altium Limited"))
      (libsource (lib "Microchip Power Mgt Charge Pump") (part "TC7662ACPA"))
    )
    (comp (ref "U3")
      (value "TC7662ACPA")
      (footprint "DIP-8")
      (description "Super Charge Pump DC-to-DC Voltage Converter, 12kHz, 8-Pin PDIP, Commercial Temperature")
      (fields (field (name "PUBLISHER") "Altium Limited"))
      (libsource (lib "Microchip Power Mgt Charge Pump") (part "TC7662ACPA"))
    )
    (comp (ref "U4")
      (value "DSPIC30F3014-20I/P")
      (footprint "DIP-40")
      (fields (field (name "PUBLISHER") "Altium Limited"))
      (libsource (lib "Microchip DSC 16-Bit dsPIC30F") (part "DSPIC30F3014-20I/P"))
    )
    (comp (ref "U5")
      (value "LM317LZ")
      (footprint "TO-92B_2")
      (description "Low-Current 1.2V to 37V Voltage Regulator")
      (fields (field (name "PUBLISHER") "Altium Limited"))
      (libsource (lib "ST Power Mgt Voltage Regulator") (part "LM317LZ"))
    )
    (comp (ref "U6")
      (value "LM337H")
      (footprint "TO-220V")
      (description "Three-Terminal Adjustable Negative Voltage Regulator")
      (fields (field (name "PUBLISHER") "Altium Limited"))
      (libsource (lib "ST Power Mgt Voltage Regulator") (part "LM337H"))
    )
    (comp (ref "U7")
      (value "TL082D")
      (footprint "DIP-8")
      (description "JFET-Input Operational Amplifier")
      (fields (field (name "PUBLISHER") "Altium Limited"))
      (libsource (lib "TI Operational Amplifier") (part "TL082D"))
    )
    (comp (ref "U8")
      (value "MULTIPLEXORADG706")
      (footprint "MULTIPLEXORADG706SMD")
      (libsource (lib "Libreria RSA") (part "MULTIPLEXORADG706"))
    )
    (comp (ref "U9") (value "INA114") (footprint "DIP-8") (libsource (lib "Libreria RSA") (part "INA114")))
    (comp (ref "U10")
      (value "TL084ACN")
      (footprint "SOIC-14")
      (description "General-Purpose J-FET Quad Operational Amplifier")
      (fields (field (name "PUBLISHER") "Altium Limited"))
      (libsource (lib "ST Operational Amplifier") (part "TL084ACN"))
    )
    (comp (ref "U11")
      (value "MULTIPLEXORADG706")
      (footprint "MULTIPLEXORADG706SMD")
      (libsource (lib "Libreria RSA") (part "MULTIPLEXORADG706"))
    )
    (comp (ref "U12") (value "INA114") (footprint "DIP-8") (libsource (lib "Libreria RSA") (part "INA114")))
    (comp (ref "U13")
      (value "TL084ACN")
      (footprint "SOIC-14")
      (description "General-Purpose J-FET Quad Operational Amplifier")
      (fields (field (name "PUBLISHER") "Altium Limited"))
      (libsource (lib "ST Operational Amplifier") (part "TL084ACN"))
    )
    (comp (ref "U14") (value "DS1307") (footprint "DIP-8") (libsource (lib "Libreria RSA") (part "DS1307")))
    (comp (ref "U15")
      (value "MULTIPLEXORADG706")
      (footprint "MULTIPLEXORADG706SMD")
      (libsource (lib "Libreria RSA") (part "MULTIPLEXORADG706"))
    )
    (comp (ref "U16") (value "INA114") (footprint "DIP-8") (libsource (lib "Libreria RSA") (part "INA114")))
    (comp (ref "U17")
      (value "TL084ACN")
      (footprint "SOIC-14")
      (description "General-Purpose J-FET Quad Operational Amplifier")
      (fields (field (name "PUBLISHER") "Altium Limited"))
      (libsource (lib "ST Operational Amplifier") (part "TL084ACN"))
    )
    (comp (ref "Y1")
      (value "XTAL-15MHz")
      (footprint "CRISTAL10MHz")
      (description "Crystal Oscillator")
      (fields (field (name "PUBLISHER") "Altium Limited"))
      (libsource (lib "Miscellaneous Devices") (part "XTAL"))
    )
    (comp (ref "Y2")
      (value "XTAL-32768")
      (footprint "CRISTAL32768")
      (description "Crystal Oscillator")
      (fields (field (name "PUBLISHER") "Altium Limited"))
      (libsource (lib "Miscellaneous Devices") (part "XTAL"))
    )
  )
  (nets
    (net (code "1") (name "+2.5V") (class "Default")
      (node (ref "C32") (pin "2") (pinfunction "2_2") (pintype "passive"))
      (node (ref "C44") (pin "2") (pinfunction "2_2") (pintype "passive"))
      (node (ref "C58") (pin "2") (pinfunction "2_2") (pintype "passive"))
      (node (ref "P3") (pin "3") (pinfunction "3_3") (pintype "passive"))
      (node (ref "U11") (pin "1") (pinfunction "VDD_1") (pintype "power_in"))
      (node (ref "U11") (pin "18") (pinfunction "EN_18") (pintype "input"))
      (node (ref "U15") (pin "1") (pinfunction "VDD_1") (pintype "power_in"))
      (node (ref "U15") (pin "18") (pinfunction "EN_18") (pintype "input"))
      (node (ref "U8") (pin "1") (pinfunction "VDD_1") (pintype "power_in"))
      (node (ref "U8") (pin "18") (pinfunction "EN_18") (pintype "input"))
    )
    (net (code "2") (name "+3.3V") (class "Default")
      (node (ref "C48") (pin "2") (pinfunction "2_2") (pintype "passive"))
      (node (ref "C49") (pin "2") (pinfunction "2_2") (pintype "passive"))
      (node (ref "P11") (pin "1") (pinfunction "1_1") (pintype "passive"))
      (node (ref "P12") (pin "1") (pinfunction "1_1") (pintype "passive"))
      (node (ref "P12") (pin "17") (pinfunction "17_17") (pintype "passive"))
      (node (ref "Q2") (pin "1") (pinfunction "G_1") (pintype "passive"))
      (node (ref "Q3") (pin "1") (pinfunction "G_1") (pintype "passive"))
      (node (ref "Q4") (pin "1") (pinfunction "G_1") (pintype "passive"))
      (node (ref "Q5") (pin "1") (pinfunction "G_1") (pintype "passive"))
      (node (ref "Q6") (pin "1") (pinfunction "G_1") (pintype "passive"))
      (node (ref "Q7") (pin "1") (pinfunction "G_1") (pintype "passive"))
      (node (ref "R120") (pin "2") (pinfunction "2_2") (pintype "passive"))
      (node (ref "R49") (pin "2") (pinfunction "2_2") (pintype "passive"))
      (node (ref "R81") (pin "2") (pinfunction "2_2") (pintype "passive"))
      (node (ref "R83") (pin "2") (pinfunction "2_2") (pintype "passive"))
      (node (ref "R94") (pin "2") (pinfunction "2_2") (pintype "passive"))
      (node (ref "R96") (pin "2") (pinfunction "2_2") (pintype "passive"))
    )
    (net (code "3") (name "+5V") (class "Default")
      (node (ref "C12") (pin "2") (pinfunction "2_2") (pintype "passive"))
      (node (ref "C13") (pin "2") (pinfunction "2_2") (pintype "passive"))
      (node (ref "C14") (pin "2") (pinfunction "2_2") (pintype "passive"))
      (node (ref "C15") (pin "2") (pinfunction "2_2") (pintype "passive"))
      (node (ref "C36") (pin "2") (pinfunction "2_2") (pintype "passive"))
      (node (ref "C40") (pin "2") (pinfunction "2_2") (pintype "passive"))
      (node (ref "C5") (pin "1") (pinfunction "1_1") (pintype "passive"))
      (node (ref "C7") (pin "2") (pinfunction "2_2") (pintype "passive"))
      (node (ref "C8") (pin "2") (pinfunction "2_2") (pintype "passive"))
      (node (ref "GPS1") (pin "1") (pinfunction "VIN_1") (pintype "passive"))
      (node (ref "P2") (pin "1") (pinfunction "1_1") (pintype "passive"))
      (node (ref "P9") (pin "2") (pinfunction "2_2") (pintype "passive"))
      (node (ref "Q1") (pin "3") (pinfunction "S_3") (pintype "passive"))
      (node (ref "R121") (pin "2") (pinfunction "2_2") (pintype "passive"))
      (node (ref "R15") (pin "1") (pinfunction "TOP_1") (pintype "passive"))
      (node (ref "R50") (pin "2") (pinfunction "2_2") (pintype "passive"))
      (node (ref "R79") (pin "1") (pinfunction "1_1") (pintype "passive"))
      (node (ref "R80") (pin "1") (pinfunction "1_1") (pintype "passive"))
      (node (ref "R82") (pin "2") (pinfunction "2_2") (pintype "passive"))
      (node (ref "R84") (pin "2") (pinfunction "2_2") (pintype "passive"))
      (node (ref "R95") (pin "2") (pinfunction "2_2") (pintype "passive"))
      (node (ref "R97") (pin "2") (pinfunction "2_2") (pintype "passive"))
      (node (ref "U1") (pin "3") (pinfunction "OUT+_3") (pintype "passive"))
      (node (ref "U14") (pin "8") (pinfunction "VCC_8") (pintype "power_in"))
      (node (ref "U4") (pin "11") (pinfunction "VDD_11") (pintype "power_in"))
      (node (ref "U4") (pin "21") (pinfunction "VDD_21") (pintype "power_in"))
      (node (ref "U4") (pin "32") (pinfunction "VDD_32") (pintype "power_in"))
      (node (ref "U4") (pin "40") (pinfunction "AVDD_40") (pintype "power_in"))
    )
    (net (code "4") (name "+12V") (class "Default")
      (node (ref "C16") (pin "1") (pinfunction "1_1") (pintype "passive"))
      (node (ref "C18") (pin "2") (pinfunction "2_2") (pintype "passive"))
      (node (ref "C25") (pin "2") (pinfunction "2_2") (pintype "passive"))
      (node (ref "C31") (pin "2") (pinfunction "2_2") (pintype "passive"))
      (node (ref "C4") (pin "1") (pinfunction "1_1") (pintype "passive"))
      (node (ref "C43") (pin "2") (pinfunction "2_2") (pintype "passive"))
      (node (ref "C57") (pin "2") (pinfunction "2_2") (pintype "passive"))
      (node (ref "C6") (pin "2") (pinfunction "2_2") (pintype "passive"))
      (node (ref "D2") (pin "2") (pinfunction "K_2") (pintype "passive"))
      (node (ref "D4") (pin "2") (pinfunction "K_2") (pintype "passive"))
      (node (ref "P7") (pin "1") (pinfunction "1_1") (pintype "passive"))
      (node (ref "R114") (pin "1") (pinfunction "1_1") (pintype "passive"))
      (node (ref "R46") (pin "1") (pinfunction "1_1") (pintype "passive"))
      (node (ref "R76") (pin "1") (pinfunction "1_1") (pintype "passive"))
      (node (ref "U1") (pin "1") (pinfunction "IN+_1") (pintype "passive"))
      (node (ref "U10") (pin "4") (pinfunction "V+_4") (pintype "power_in"))
      (node (ref "U13") (pin "4") (pinfunction "V+_4") (pintype "power_in"))
      (node (ref "U17") (pin "4") (pinfunction "V+_4") (pintype "power_in"))
      (node (ref "U2") (pin "8") (pinfunction "VDD_8") (pintype "power_in"))
      (node (ref "U3") (pin "8") (pinfunction "VDD_8") (pintype "power_in"))
      (node (ref "U5") (pin "2") (pinfunction "IN_2") (pintype "power_in"))
      (node (ref "U7") (pin "8") (pinfunction "V+_8") (pintype "power_in"))
    )
    (net (code "5") (name "-2.5V") (class "Default")
      (node (ref "C33") (pin "2") (pinfunction "2_2") (pintype "passive"))
      (node (ref "C45") (pin "2") (pinfunction "2_2") (pintype "passive"))
      (node (ref "C59") (pin "2") (pinfunction "2_2") (pintype "passive"))
      (node (ref "P4") (pin "3") (pinfunction "3_3") (pintype "passive"))
      (node (ref "U11") (pin "27") (pinfunction "VSS_27") (pintype "power_in"))
      (node (ref "U15") (pin "27") (pinfunction "VSS_27") (pintype "power_in"))
      (node (ref "U8") (pin "27") (pinfunction "VSS_27") (pintype "power_in"))
    )
    (net (code "6") (name "-12V") (class "Default")
      (node (ref "C1") (pin "2") (pinfunction "2_2") (pintype "passive"))
      (node (ref "C19") (pin "2") (pinfunction "2_2") (pintype "passive"))
      (node (ref "C2") (pin "1") (pinfunction "1_1") (pintype "passive"))
      (node (ref "C21") (pin "2") (pinfunction "2_2") (pintype "passive"))
      (node (ref "C24") (pin "2") (pinfunction "2_2") (pintype "passive"))
      (node (ref "C28") (pin "2") (pinfunction "2_2") (pintype "passive"))
      (node (ref "C39") (pin "2") (pinfunction "2_2") (pintype "passive"))
      (node (ref "C54") (pin "2") (pinfunction "2_2") (pintype "passive"))
      (node (ref "P7") (pin "3") (pinfunction "3_3") (pintype "passive"))
      (node (ref "R113") (pin "1") (pinfunction "1_1") (pintype "passive"))
      (node (ref "R45") (pin "1") (pinfunction "1_1") (pintype "passive"))
      (node (ref "R75") (pin "1") (pinfunction "1_1") (pintype "passive"))
      (node (ref "U10") (pin "11") (pinfunction "V-_11") (pintype "power_in"))
      (node (ref "U13") (pin "11") (pinfunction "V-_11") (pintype "power_in"))
      (node (ref "U17") (pin "11") (pinfunction "V-_11") (pintype "power_in"))
      (node (ref "U2") (pin "5") (pinfunction "VOUT_5") (pintype "power_in"))
      (node (ref "U3") (pin "5") (pinfunction "VOUT_5") (pintype "power_in"))
      (node (ref "U6") (pin "3") (pinfunction "IN_3") (pintype "power_in"))
      (node (ref "U7") (pin "4") (pinfunction "V-_4") (pintype "power_in"))
    )
    (net (code "7") (name "5V_RPi") (class "Default")
      (node (ref "C50") (pin "2") (pinfunction "2_2") (pintype "passive"))
      (node (ref "C51") (pin "2") (pinfunction "2_2") (pintype "passive"))
      (node (ref "P12") (pin "2") (pinfunction "2_2") (pintype "passive"))
      (node (ref "P12") (pin "4") (pinfunction "4_4") (pintype "passive"))
      (node (ref "P8") (pin "2") (pinfunction "2_2") (pintype "passive"))
    )
    (net (code "8") (name "A0") (class "Default")
      (node (ref "R14") (pin "2") (pinfunction "2_2") (pintype "passive"))
      (node (ref "R5") (pin "1") (pinfunction "1_1") (pintype "passive"))
      (node (ref "U11") (pin "17") (pinfunction "A0_17") (pintype "input"))
      (node (ref "U15") (pin "17") (pinfunction "A0_17") (pintype "input"))
      (node (ref "U8") (pin "17") (pinfunction "A0_17") (pintype "input"))
    )
    (net (code "9") (name "A1") (class "Default")
      (node (ref "R13") (pin "2") (pinfunction "2_2") (pintype "passive"))
      (node (ref "R4") (pin "1") (pinfunction "1_1") (pintype "passive"))
      (node (ref "U11") (pin "16") (pinfunction "A1_16") (pintype "input"))
      (node (ref "U15") (pin "16") (pinfunction "A1_16") (pintype "input"))
      (node (ref "U8") (pin "16") (pinfunction "A1_16") (pintype "input"))
    )
    (net (code "10") (name "A2") (class "Default")
      (node (ref "R12") (pin "2") (pinfunction "2_2") (pintype "passive"))
      (node (ref "R3") (pin "1") (pinfunction "1_1") (pintype "passive"))
      (node (ref "U11") (pin "15") (pinfunction "A2_15") (pintype "input"))
      (node (ref "U15") (pin "15") (pinfunction "A2_15") (pintype "input"))
      (node (ref "U8") (pin "15") (pinfunction "A2_15") (pintype "input"))
    )
    (net (code "11") (name "A3") (class "Default")
      (node (ref "R11") (pin "2") (pinfunction "2_2") (pintype "passive"))
      (node (ref "R2") (pin "1") (pinfunction "1_1") (pintype "passive"))
      (node (ref "U11") (pin "14") (pinfunction "A3_14") (pintype "input"))
      (node (ref "U15") (pin "14") (pinfunction "A3_14") (pintype "input"))
      (node (ref "U8") (pin "14") (pinfunction "A3_14") (pintype "input"))
    )
    (net (code "12") (name "C1+") (class "Default")
      (node (ref "P6") (pin "1") (pinfunction "1_1") (pintype "passive"))
      (node (ref "R33") (pin "1") (pinfunction "1_1") (pintype "passive"))
      (node (ref "U9") (pin "3") (pinfunction "3_3") (pintype "input"))
    )
    (net (code "13") (name "C1-") (class "Default")
      (node (ref "P6") (pin "2") (pinfunction "2_2") (pintype "passive"))
      (node (ref "R23") (pin "2") (pinfunction "2_2") (pintype "passive"))
      (node (ref "U9") (pin "2") (pinfunction "2_2") (pintype "input"))
    )
    (net (code "14") (name "C2+") (class "Default")
      (node (ref "P6") (pin "3") (pinfunction "3_3") (pintype "passive"))
      (node (ref "R65") (pin "1") (pinfunction "1_1") (pintype "passive"))
      (node (ref "U12") (pin "3") (pinfunction "3_3") (pintype "input"))
    )
    (net (code "15") (name "C2-") (class "Default")
      (node (ref "P6") (pin "4") (pinfunction "4_4") (pintype "passive"))
      (node (ref "R56") (pin "2") (pinfunction "2_2") (pintype "passive"))
      (node (ref "U12") (pin "2") (pinfunction "2_2") (pintype "input"))
    )
    (net (code "16") (name "C3+") (class "Default")
      (node (ref "P6") (pin "5") (pinfunction "5_5") (pintype "passive"))
      (node (ref "R103") (pin "1") (pinfunction "1_1") (pintype "passive"))
      (node (ref "U16") (pin "3") (pinfunction "3_3") (pintype "input"))
    )
    (net (code "17") (name "C3-") (class "Default")
      (node (ref "P6") (pin "6") (pinfunction "6_6") (pintype "passive"))
      (node (ref "R90") (pin "2") (pinfunction "2_2") (pintype "passive"))
      (node (ref "U16") (pin "2") (pinfunction "2_2") (pintype "input"))
    )
    (net (code "18") (name "CS_3.3V") (class "Default")
      (node (ref "P12") (pin "24") (pinfunction "24_24") (pintype "passive"))
      (node (ref "Q3") (pin "2") (pinfunction "S_2") (pintype "passive"))
      (node (ref "R81") (pin "1") (pinfunction "1_1") (pintype "passive"))
    )
    (net (code "19") (name "CS_5V") (class "Default")
      (node (ref "Q3") (pin "3") (pinfunction "D_3") (pintype "passive"))
      (node (ref "R82") (pin "1") (pinfunction "1_1") (pintype "passive"))
      (node (ref "U4") (pin "4") (pinfunction "AN2/~{SS1}/LVDIN/CN4/RB2_4") (pintype "bidirectional"))
    )
    (net (code "20") (name "Cristal1") (class "Default")
      (node (ref "C3") (pin "1") (pinfunction "1_1") (pintype "passive"))
      (node (ref "U4") (pin "13") (pinfunction "OSC1/CLKI_13") (pintype "input"))
      (node (ref "Y1") (pin "2") (pinfunction "OSC2_2") (pintype "passive"))
    )
    (net (code "21") (name "Cristal2") (class "Default")
      (node (ref "C11") (pin "1") (pinfunction "1_1") (pintype "passive"))
      (node (ref "U4") (pin "14") (pinfunction "OSC2/CLKO/RC15_14") (pintype "bidirectional"))
      (node (ref "Y1") (pin "1") (pinfunction "OSC1_1") (pintype "passive"))
    )
    (net (code "22") (name "EN_GPS") (class "Default")
      (node (ref "GPS1") (pin "7") (pinfunction "EN_7") (pintype "passive"))
      (node (ref "U4") (pin "19") (pinfunction "RD3_19") (pintype "bidirectional"))
    )
    (net (code "23") (name "GND") (class "Default")
      (node (ref "BT1") (pin "1") (pinfunction "-_1") (pintype "passive"))
      (node (ref "C1") (pin "1") (pinfunction "1_1") (pintype "passive"))
      (node (ref "C11") (pin "2") (pinfunction "2_2") (pintype "passive"))
      (node (ref "C12") (pin "1") (pinfunction "1_1") (pintype "passive"))
      (node (ref "C13") (pin "1") (pinfunction "1_1") (pintype "passive"))
      (node (ref "C14") (pin "1") (pinfunction "1_1") (pintype "passive"))
      (node (ref "C15") (pin "1") (pinfunction "1_1") (pintype "passive"))
      (node (ref "C16") (pin "2") (pinfunction "2_2") (pintype "passive"))
      (node (ref "C17") (pin "2") (pinfunction "2_2") (pintype "passive"))
      (node (ref "C18") (pin "1") (pinfunction "1_1") (pintype "passive"))
      (node (ref "C19") (pin "1") (pinfunction "1_1") (pintype "passive"))
      (node (ref "C2") (pin "2") (pinfunction "2_2") (pintype "passive"))
      (node (ref "C20") (pin "1") (pinfunction "1_1") (pintype "passive"))
      (node (ref "C21") (pin "1") (pinfunction "1_1") (pintype "passive"))
      (node (ref "C22") (pin "1") (pinfunction "1_1") (pintype "passive"))
      (node (ref "C23") (pin "1") (pinfunction "1_1") (pintype "passive"))
      (node (ref "C24") (pin "1") (pinfunction "1_1") (pintype "passive"))
      (node (ref "C25") (pin "1") (pinfunction "1_1") (pintype "passive"))
      (node (ref "C28") (pin "1") (pinfunction "1_1") (pintype "passive"))
      (node (ref "C29") (pin "2") (pinfunction "2_2") (pintype "passive"))
      (node (ref "C3") (pin "2") (pinfunction "2_2") (pintype "passive"))
      (node (ref "C30") (pin "2") (pinfunction "2_2") (pintype "passive"))
      (node (ref "C31") (pin "1") (pinfunction "1_1") (pintype "passive"))
      (node (ref "C32") (pin "1") (pinfunction "1_1") (pintype "passive"))
      (node (ref "C33") (pin "1") (pinfunction "1_1") (pintype "passive"))
      (node (ref "C34") (pin "1") (pinfunction "1_1") (pintype "passive"))
      (node (ref "C35") (pin "1") (pinfunction "1_1") (pintype "passive"))
      (node (ref "C36") (pin "1") (pinfunction "1_1") (pintype "passive"))
      (node (ref "C39") (pin "1") (pinfunction "1_1") (pintype "passive"))
      (node (ref "C4") (pin "2") (pinfunction "2_2") (pintype "passive"))
      (node (ref "C40") (pin "1") (pinfunction "1_1") (pintype "passive"))
      (node (ref "C41") (pin "2") (pinfunction "2_2") (pintype "passive"))
      (node (ref "C42") (pin "2") (pinfunction "2_2") (pintype "passive"))
      (node (ref "C43") (pin "1") (pinfunction "1_1") (pintype "passive"))
      (node (ref "C44") (pin "1") (pinfunction "1_1") (pintype "passive"))
      (node (ref "C45") (pin "1") (pinfunction "1_1") (pintype "passive"))
      (node (ref "C46") (pin "1") (pinfunction "1_1") (pintype "passive"))
      (node (ref "C47") (pin "1") (pinfunction "1_1") (pintype "passive"))
      (node (ref "C48") (pin "1") (pinfunction "1_1") (pintype "passive"))
      (node (ref "C49") (pin "1") (pinfunction "1_1") (pintype "passive"))
      (node (ref "C5") (pin "2") (pinfunction "2_2") (pintype "passive"))
      (node (ref "C50") (pin "1") (pinfunction "1_1") (pintype "passive"))
      (node (ref "C51") (pin "1") (pinfunction "1_1") (pintype "passive"))
      (node (ref "C54") (pin "1") (pinfunction "1_1") (pintype "passive"))
      (node (ref "C55") (pin "2") (pinfunction "2_2") (pintype "passive"))
      (node (ref "C56") (pin "2") (pinfunction "2_2") (pintype "passive"))
      (node (ref "C57") (pin "1") (pinfunction "1_1") (pintype "passive"))
      (node (ref "C58") (pin "1") (pinfunction "1_1") (pintype "passive"))
      (node (ref "C59") (pin "1") (pinfunction "1_1") (pintype "passive"))
      (node (ref "C6") (pin "1") (pinfunction "1_1") (pintype "passive"))
      (node (ref "C60") (pin "1") (pinfunction "1_1") (pintype "passive"))
      (node (ref "C61") (pin "1") (pinfunction "1_1") (pintype "passive"))
      (node (ref "C7") (pin "1") (pinfunction "1_1") (pintype "passive"))
      (node (ref "C8") (pin "1") (pinfunction "1_1") (pintype "passive"))
      (node (ref "D1") (pin "1") (pinfunction "A_1") (pintype "passive"))
      (node (ref "D3") (pin "1") (pinfunction "A_1") (pintype "passive"))
      (node (ref "GPS1") (pin "2") (pinfunction "GND_2") (pintype "passive"))
      (node (ref "P11") (pin "2") (pinfunction "2_2") (pintype "passive"))
      (node (ref "P12") (pin "14") (pinfunction "14_14") (pintype "passive"))
      (node (ref "P12") (pin "20") (pinfunction "20_20") (pintype "passive"))
      (node (ref "P12") (pin "25") (pinfunction "25_25") (pintype "passive"))
      (node (ref "P12") (pin "30") (pinfunction "30_30") (pintype "passive"))
      (node (ref "P12") (pin "34") (pinfunction "34_34") (pintype "passive"))
      (node (ref "P12") (pin "39") (pinfunction "39_39") (pintype "passive"))
      (node (ref "P12") (pin "6") (pinfunction "6_6") (pintype "passive"))
      (node (ref "P12") (pin "9") (pinfunction "9_9") (pintype "passive"))
      (node (ref "P13") (pin "2") (pinfunction "2_2") (pintype "passive"))
      (node (ref "P13") (pin "4") (pinfunction "4_4") (pintype "passive"))
      (node (ref "P2") (pin "2") (pinfunction "2_2") (pintype "passive"))
      (node (ref "P5") (pin "2") (pinfunction "2_2") (pintype "passive"))
      (node (ref "P5") (pin "4") (pinfunction "4_4") (pintype "passive"))
      (node (ref "P7") (pin "2") (pinfunction "2_2") (pintype "passive"))
      (node (ref "P7") (pin "4") (pinfunction "4_4") (pintype "passive"))
      (node (ref "P9") (pin "3") (pinfunction "3_3") (pintype "passive"))
      (node (ref "R103") (pin "2") (pinfunction "2_2") (pintype "passive"))
      (node (ref "R11") (pin "1") (pinfunction "1_1") (pintype "passive"))
      (node (ref "R116") (pin "2") (pinfunction "2_2") (pintype "passive"))
      (node (ref "R119") (pin "1") (pinfunction "1_1") (pintype "passive"))
      (node (ref "R12") (pin "1") (pinfunction "1_1") (pintype "passive"))
      (node (ref "R13") (pin "1") (pinfunction "1_1") (pintype "passive"))
      (node (ref "R14") (pin "1") (pinfunction "1_1") (pintype "passive"))
      (node (ref "R15") (pin "2") (pinfunction "BOT_2") (pintype "passive"))
      (node (ref "R18") (pin "1") (pinfunction "1_1") (pintype "passive"))
      (node (ref "R19") (pin "1") (pinfunction "1_1") (pintype "passive"))
      (node (ref "R23") (pin "1") (pinfunction "1_1") (pintype "passive"))
      (node (ref "R26") (pin "1") (pinfunction "1_1") (pintype "passive"))
      (node (ref "R33") (pin "2") (pinfunction "2_2") (pintype "passive"))
      (node (ref "R48") (pin "2") (pinfunction "2_2") (pintype "passive"))
      (node (ref "R56") (pin "1") (pinfunction "1_1") (pintype "passive"))
      (node (ref "R65") (pin "2") (pinfunction "2_2") (pintype "passive"))
      (node (ref "R78") (pin "2") (pinfunction "2_2") (pintype "passive"))
      (node (ref "R8") (pin "3") (pinfunction "TAP_3") (pintype "passive"))
      (node (ref "R9") (pin "3") (pinfunction "TAP_3") (pintype "passive"))
      (node (ref "R90") (pin "1") (pinfunction "1_1") (pintype "passive"))
      (node (ref "U1") (pin "2") (pinfunction "IN-_2") (pintype "passive"))
      (node (ref "U1") (pin "4") (pinfunction "OUT-_4") (pintype "passive"))
      (node (ref "U11") (pin "12") (pinfunction "GND_12") (pintype "power_in"))
      (node (ref "U12") (pin "5") (pinfunction "5_5") (pintype "power_in"))
      (node (ref "U14") (pin "4") (pinfunction "GND_4") (pintype "power_in"))
      (node (ref "U15") (pin "12") (pinfunction "GND_12") (pintype "power_in"))
      (node (ref "U16") (pin "5") (pinfunction "5_5") (pintype "power_in"))
      (node (ref "U2") (pin "3") (pinfunction "GND_3") (pintype "power_in"))
      (node (ref "U3") (pin "3") (pinfunction "GND_3") (pintype "power_in"))
      (node (ref "U4") (pin "12") (pinfunction "VSS_12") (pintype "power_in"))
      (node (ref "U4") (pin "20") (pinfunction "VSS_20") (pintype "power_in"))
      (node (ref "U4") (pin "31") (pinfunction "VSS_31") (pintype "power_in"))
      (node (ref "U4") (pin "39") (pinfunction "AVSS_39") (pintype "power_in"))
      (node (ref "U8") (pin "12") (pinfunction "GND_12") (pintype "power_in"))
      (node (ref "U9") (pin "5") (pinfunction "5_5") (pintype "power_in"))
    )
    (net (code "24") (name "INT_FROM_PIC") (class "Default")
      (node (ref "P12") (pin "11") (pinfunction "11_11") (pintype "passive"))
      (node (ref "R16") (pin "1") (pinfunction "1_1") (pintype "passive"))
      (node (ref "R18") (pin "2") (pinfunction "2_2") (pintype "passive"))
    )
    (net (code "25") (name "INreloj") (class "Default")
      (node (ref "U14") (pin "7") (pinfunction "OUT_7") (pintype "output"))
      (node (ref "U4") (pin "18") (pinfunction "IC2/INT2/RD9_18") (pintype "bidirectional"))
    )
    (net (code "26") (name "LED_PIC_1") (class "Default")
      (node (ref "P5") (pin "1") (pinfunction "1_1") (pintype "passive"))
      (node (ref "R1") (pin "1") (pinfunction "1_1") (pintype "passive"))
    )
    (net (code "27") (name "LED_PIC_2") (class "Default")
      (node (ref "P5") (pin "3") (pinfunction "3_3") (pintype "passive"))
      (node (ref "R10") (pin "1") (pinfunction "1_1") (pintype "passive"))
    )
    (net (code "28") (name "LED_RPi_1") (class "Default")
      (node (ref "P13") (pin "1") (pinfunction "1_1") (pintype "passive"))
      (node (ref "R117") (pin "1") (pinfunction "1_1") (pintype "passive"))
    )
    (net (code "29") (name "LED_RPi_2") (class "Default")
      (node (ref "P13") (pin "3") (pinfunction "3_3") (pintype "passive"))
      (node (ref "R118") (pin "1") (pinfunction "1_1") (pintype "passive"))
    )
    (net (code "30") (name "MCLR") (class "Default")
      (node (ref "P10") (pin "2") (pinfunction "2_2") (pintype "passive"))
      (node (ref "P9") (pin "1") (pinfunction "1_1") (pintype "passive"))
      (node (ref "U4") (pin "1") (pinfunction "~{MCLR}_1") (pintype "input"))
    )
    (net (code "31") (name "MISO_3.3V") (class "Default")
      (node (ref "P12") (pin "21") (pinfunction "21_21") (pintype "passive"))
      (node (ref "R17") (pin "1") (pinfunction "1_1") (pintype "passive"))
      (node (ref "R19") (pin "2") (pinfunction "2_2") (pintype "passive"))
    )
    (net (code "32") (name "MOSI_3.3V") (class "Default")
      (node (ref "P12") (pin "19") (pinfunction "19_19") (pintype "passive"))
      (node (ref "Q4") (pin "2") (pinfunction "S_2") (pintype "passive"))
      (node (ref "R83") (pin "1") (pinfunction "1_1") (pintype "passive"))
    )
    (net (code "33") (name "MOSI_5V") (class "Default")
      (node (ref "Q4") (pin "3") (pinfunction "D_3") (pintype "passive"))
      (node (ref "R84") (pin "1") (pinfunction "1_1") (pintype "passive"))
      (node (ref "U4") (pin "26") (pinfunction "U1RX/SDI1/SDA/RF2_26") (pintype "bidirectional"))
    )
    (net (code "34") (name "Net-(BT1-+)") (class "Default")
      (node (ref "BT1") (pin "0") (pinfunction "+_0") (pintype "passive"))
      (node (ref "U14") (pin "3") (pinfunction "Vbat_3") (pintype "power_in"))
    )
    (net (code "35") (name "Net-(C26-Pad2)") (class "Default")
      (node (ref "C26") (pin "2") (pinfunction "2_2") (pintype "passive"))
      (node (ref "R31") (pin "2") (pinfunction "2_2") (pintype "passive"))
      (node (ref "R32") (pin "1") (pinfunction "1_1") (pintype "passive"))
    )
    (net (code "36") (name "Net-(C27-Pad2)") (class "Default")
      (node (ref "C27") (pin "2") (pinfunction "2_2") (pintype "passive"))
      (node (ref "R35") (pin "2") (pinfunction "2_2") (pintype "passive"))
      (node (ref "R36") (pin "1") (pinfunction "1_1") (pintype "passive"))
    )
    (net (code "37") (name "Net-(C34-Pad2)") (class "Default")
      (node (ref "C34") (pin "2") (pinfunction "2_2") (pintype "passive"))
      (node (ref "R45") (pin "2") (pinfunction "2_2") (pintype "passive"))
      (node (ref "U9") (pin "4") (pinfunction "4_4") (pintype "power_in"))
    )
    (net (code "38") (name "Net-(C35-Pad2)") (class "Default")
      (node (ref "C35") (pin "2") (pinfunction "2_2") (pintype "passive"))
      (node (ref "R46") (pin "2") (pinfunction "2_2") (pintype "passive"))
      (node (ref "U9") (pin "7") (pinfunction "7_7") (pintype "power_in"))
    )
    (net (code "39") (name "Net-(C37-Pad2)") (class "Default")
      (node (ref "C37") (pin "2") (pinfunction "2_2") (pintype "passive"))
      (node (ref "R62") (pin "2") (pinfunction "2_2") (pintype "passive"))
      (node (ref "R63") (pin "1") (pinfunction "1_1") (pintype "passive"))
    )
    (net (code "40") (name "Net-(C38-Pad2)") (class "Default")
      (node (ref "C38") (pin "2") (pinfunction "2_2") (pintype "passive"))
      (node (ref "R66") (pin "2") (pinfunction "2_2") (pintype "passive"))
      (node (ref "R67") (pin "1") (pinfunction "1_1") (pintype "passive"))
    )
    (net (code "41") (name "Net-(C46-Pad2)") (class "Default")
      (node (ref "C46") (pin "2") (pinfunction "2_2") (pintype "passive"))
      (node (ref "R75") (pin "2") (pinfunction "2_2") (pintype "passive"))
      (node (ref "U12") (pin "4") (pinfunction "4_4") (pintype "power_in"))
    )
    (net (code "42") (name "Net-(C47-Pad2)") (class "Default")
      (node (ref "C47") (pin "2") (pinfunction "2_2") (pintype "passive"))
      (node (ref "R76") (pin "2") (pinfunction "2_2") (pintype "passive"))
      (node (ref "U12") (pin "7") (pinfunction "7_7") (pintype "power_in"))
    )
    (net (code "43") (name "Net-(C52-Pad2)") (class "Default")
      (node (ref "C52") (pin "2") (pinfunction "2_2") (pintype "passive"))
      (node (ref "R100") (pin "2") (pinfunction "2_2") (pintype "passive"))
      (node (ref "R101") (pin "1") (pinfunction "1_1") (pintype "passive"))
    )
    (net (code "44") (name "Net-(C53-Pad2)") (class "Default")
      (node (ref "C53") (pin "2") (pinfunction "2_2") (pintype "passive"))
      (node (ref "R104") (pin "2") (pinfunction "2_2") (pintype "passive"))
      (node (ref "R105") (pin "1") (pinfunction "1_1") (pintype "passive"))
    )
    (net (code "45") (name "Net-(C60-Pad2)") (class "Default")
      (node (ref "C60") (pin "2") (pinfunction "2_2") (pintype "passive"))
      (node (ref "R113") (pin "2") (pinfunction "2_2") (pintype "passive"))
      (node (ref "U16") (pin "4") (pinfunction "4_4") (pintype "power_in"))
    )
    (net (code "46") (name "Net-(C61-Pad2)") (class "Default")
      (node (ref "C61") (pin "2") (pinfunction "2_2") (pintype "passive"))
      (node (ref "R114") (pin "2") (pinfunction "2_2") (pintype "passive"))
      (node (ref "U16") (pin "7") (pinfunction "7_7") (pintype "power_in"))
    )
    (net (code "47") (name "Net-(D1-K)") (class "Default")
      (node (ref "D1") (pin "2") (pinfunction "K_2") (pintype "passive"))
      (node (ref "D2") (pin "1") (pinfunction "A_1") (pintype "passive"))
      (node (ref "P1") (pin "1") (pinfunction "1_1") (pintype "passive"))
    )
    (net (code "48") (name "Net-(D3-K)") (class "Default")
      (node (ref "D3") (pin "2") (pinfunction "K_2") (pintype "passive"))
      (node (ref "D4") (pin "1") (pinfunction "A_1") (pintype "passive"))
      (node (ref "P1") (pin "2") (pinfunction "2_2") (pintype "passive"))
    )
    (net (code "49") (name "Net-(P12-Pad32)") (class "Default")
      (node (ref "P12") (pin "32") (pinfunction "32_32") (pintype "passive"))
      (node (ref "R117") (pin "2") (pinfunction "2_2") (pintype "passive"))
    )
    (net (code "50") (name "Net-(P12-Pad36)") (class "Default")
      (node (ref "P12") (pin "36") (pinfunction "36_36") (pintype "passive"))
      (node (ref "R118") (pin "2") (pinfunction "2_2") (pintype "passive"))
    )
    (net (code "51") (name "Net-(Q1-D)") (class "Default")
      (node (ref "P8") (pin "1") (pinfunction "1_1") (pintype "passive"))
      (node (ref "Q1") (pin "1") (pinfunction "D_1") (pintype "passive"))
    )
    (net (code "52") (name "Net-(R8-TOP)") (class "Default")
      (node (ref "R6") (pin "1") (pinfunction "1_1") (pintype "passive"))
      (node (ref "R8") (pin "1") (pinfunction "TOP_1") (pintype "passive"))
      (node (ref "U5") (pin "1") (pinfunction "ADJ_1") (pintype "input"))
    )
    (net (code "53") (name "Net-(R9-TOP)") (class "Default")
      (node (ref "R7") (pin "1") (pinfunction "1_1") (pintype "passive"))
      (node (ref "R9") (pin "1") (pinfunction "TOP_1") (pintype "passive"))
      (node (ref "U6") (pin "1") (pinfunction "ADJ_1") (pintype "input"))
    )
    (net (code "54") (name "Net-(R15-TAP)") (class "Default")
      (node (ref "R15") (pin "3") (pinfunction "TAP_3") (pintype "passive"))
      (node (ref "U7") (pin "3") (pinfunction "IN+_3") (pintype "input"))
    )
    (net (code "55") (name "Net-(R31-Pad1)") (class "Default")
      (node (ref "R31") (pin "1") (pinfunction "1_1") (pintype "passive"))
      (node (ref "U9") (pin "6") (pinfunction "6_6") (pintype "output"))
    )
    (net (code "56") (name "Net-(R62-Pad1)") (class "Default")
      (node (ref "R62") (pin "1") (pinfunction "1_1") (pintype "passive"))
      (node (ref "U12") (pin "6") (pinfunction "6_6") (pintype "output"))
    )
    (net (code "57") (name "Net-(R100-Pad1)") (class "Default")
      (node (ref "R100") (pin "1") (pinfunction "1_1") (pintype "passive"))
      (node (ref "U16") (pin "6") (pinfunction "6_6") (pintype "output"))
    )
    (net (code "58") (name "Net-(U2-C+)") (class "Default")
      (node (ref "C9") (pin "1") (pinfunction "1_1") (pintype "passive"))
      (node (ref "U2") (pin "2") (pinfunction "C+_2") (pintype "passive"))
    )
    (net (code "59") (name "Net-(U2-C-)") (class "Default")
      (node (ref "C9") (pin "2") (pinfunction "2_2") (pintype "passive"))
      (node (ref "U2") (pin "4") (pinfunction "C-_4") (pintype "passive"))
    )
    (net (code "60") (name "Net-(U3-C+)") (class "Default")
      (node (ref "C10") (pin "1") (pinfunction "1_1") (pintype "passive"))
      (node (ref "U3") (pin "2") (pinfunction "C+_2") (pintype "passive"))
    )
    (net (code "61") (name "Net-(U3-C-)") (class "Default")
      (node (ref "C10") (pin "2") (pinfunction "2_2") (pintype "passive"))
      (node (ref "U3") (pin "4") (pinfunction "C-_4") (pintype "passive"))
    )
    (net (code "62") (name "Net-(U4-AN0{slash}VREF+{slash}CN2{slash}RB0)") (class "Default")
      (node (ref "R1") (pin "2") (pinfunction "2_2") (pintype "passive"))
      (node (ref "U4") (pin "2") (pinfunction "AN0/VREF+/CN2/RB0_2") (pintype "bidirectional"))
    )
    (net (code "63") (name "Net-(U4-AN3{slash}CN5{slash}RB3)") (class "Default")
      (node (ref "R5") (pin "2") (pinfunction "2_2") (pintype "passive"))
      (node (ref "U4") (pin "5") (pinfunction "AN3/CN5/RB3_5") (pintype "bidirectional"))
    )
    (net (code "64") (name "Net-(U4-AN4{slash}CN6{slash}RB4)") (class "Default")
      (node (ref "R4") (pin "2") (pinfunction "2_2") (pintype "passive"))
      (node (ref "U4") (pin "6") (pinfunction "AN4/CN6/RB4_6") (pintype "bidirectional"))
    )
    (net (code "65") (name "Net-(U4-AN5{slash}CN7{slash}RB5)") (class "Default")
      (node (ref "R3") (pin "2") (pinfunction "2_2") (pintype "passive"))
      (node (ref "U4") (pin "7") (pinfunction "AN5/CN7/RB5_7") (pintype "bidirectional"))
    )
    (net (code "66") (name "Net-(U4-EMUC2{slash}OC1{slash}RD0)") (class "Default")
      (node (ref "R10") (pin "2") (pinfunction "2_2") (pintype "passive"))
      (node (ref "U4") (pin "34") (pinfunction "EMUC2/OC1/RD0_34") (pintype "bidirectional"))
    )
    (net (code "67") (name "Net-(U4-EMUD3{slash}U1TX{slash}SDO1{slash}SCL{slash}RF3)") (class "Default")
      (node (ref "R17") (pin "2") (pinfunction "2_2") (pintype "passive"))
      (node (ref "U4") (pin "25") (pinfunction "EMUD3/U1TX/SDO1/SCL/RF3_25") (pintype "bidirectional"))
    )
    (net (code "68") (name "Net-(U4-RF1)") (class "Default")
      (node (ref "R16") (pin "2") (pinfunction "2_2") (pintype "passive"))
      (node (ref "U4") (pin "29") (pinfunction "RF1_29") (pintype "bidirectional"))
    )
    (net (code "69") (name "Net-(U5-OUT)") (class "Default")
      (node (ref "C17") (pin "1") (pinfunction "1_1") (pintype "passive"))
      (node (ref "C20") (pin "2") (pinfunction "2_2") (pintype "passive"))
      (node (ref "P3") (pin "2") (pinfunction "2_2") (pintype "passive"))
      (node (ref "R6") (pin "2") (pinfunction "2_2") (pintype "passive"))
      (node (ref "U5") (pin "3") (pinfunction "OUT_3") (pintype "power_in"))
    )
    (net (code "70") (name "Net-(U6-OUT)") (class "Default")
      (node (ref "C22") (pin "2") (pinfunction "2_2") (pintype "passive"))
      (node (ref "C23") (pin "2") (pinfunction "2_2") (pintype "passive"))
      (node (ref "P4") (pin "2") (pinfunction "2_2") (pintype "passive"))
      (node (ref "R7") (pin "2") (pinfunction "2_2") (pintype "passive"))
      (node (ref "U6") (pin "2") (pinfunction "OUT_2") (pintype "power_in"))
    )
    (net (code "71") (name "Net-(U8-S1)") (class "Default")
      (node (ref "R20") (pin "2") (pinfunction "2_2") (pintype "passive"))
      (node (ref "U8") (pin "19") (pinfunction "S1_19") (pintype "input"))
    )
    (net (code "72") (name "Net-(U8-S2)") (class "Default")
      (node (ref "R21") (pin "2") (pinfunction "2_2") (pintype "passive"))
      (node (ref "U8") (pin "20") (pinfunction "S2_20") (pintype "input"))
    )
    (net (code "73") (name "Net-(U8-S3)") (class "Default")
      (node (ref "R22") (pin "2") (pinfunction "2_2") (pintype "passive"))
      (node (ref "U8") (pin "21") (pinfunction "S3_21") (pintype "input"))
    )
    (net (code "74") (name "Net-(U8-S4)") (class "Default")
      (node (ref "R24") (pin "2") (pinfunction "2_2") (pintype "passive"))
      (node (ref "U8") (pin "22") (pinfunction "S4_22") (pintype "input"))
    )
    (net (code "75") (name "Net-(U8-S5)") (class "Default")
      (node (ref "R25") (pin "2") (pinfunction "2_2") (pintype "passive"))
      (node (ref "U8") (pin "23") (pinfunction "S5_23") (pintype "input"))
    )
    (net (code "76") (name "Net-(U8-S6)") (class "Default")
      (node (ref "R27") (pin "2") (pinfunction "2_2") (pintype "passive"))
      (node (ref "U8") (pin "24") (pinfunction "S6_24") (pintype "input"))
    )
    (net (code "77") (name "Net-(U8-S7)") (class "Default")
      (node (ref "R28") (pin "2") (pinfunction "2_2") (pintype "passive"))
      (node (ref "U8") (pin "25") (pinfunction "S7_25") (pintype "input"))
    )
    (net (code "78") (name "Net-(U8-S8)") (class "Default")
      (node (ref "R29") (pin "2") (pinfunction "2_2") (pintype "passive"))
      (node (ref "U8") (pin "26") (pinfunction "S8_26") (pintype "input"))
    )
    (net (code "79") (name "Net-(U8-S9)") (class "Default")
      (node (ref "R30") (pin "2") (pinfunction "2_2") (pintype "passive"))
      (node (ref "U8") (pin "11") (pinfunction "S9_11") (pintype "input"))
    )
    (net (code "80") (name "Net-(U8-S10)") (class "Default")
      (node (ref "R34") (pin "2") (pinfunction "2_2") (pintype "passive"))
      (node (ref "U8") (pin "10") (pinfunction "S10_10") (pintype "input"))
    )
    (net (code "81") (name "Net-(U8-S11)") (class "Default")
      (node (ref "R37") (pin "2") (pinfunction "2_2") (pintype "passive"))
      (node (ref "U8") (pin "9") (pinfunction "S11_9") (pintype "input"))
    )
    (net (code "82") (name "Net-(U8-S12)") (class "Default")
      (node (ref "R39") (pin "2") (pinfunction "2_2") (pintype "passive"))
      (node (ref "U8") (pin "8") (pinfunction "S12_8") (pintype "input"))
    )
    (net (code "83") (name "Net-(U8-S13)") (class "Default")
      (node (ref "R40") (pin "2") (pinfunction "2_2") (pintype "passive"))
      (node (ref "U8") (pin "7") (pinfunction "S13_7") (pintype "input"))
    )
    (net (code "84") (name "Net-(U8-S14)") (class "Default")
      (node (ref "R41") (pin "2") (pinfunction "2_2") (pintype "passive"))
      (node (ref "U8") (pin "6") (pinfunction "S14_6") (pintype "input"))
    )
    (net (code "85") (name "Net-(U8-S15)") (class "Default")
      (node (ref "R42") (pin "2") (pinfunction "2_2") (pintype "passive"))
      (node (ref "U8") (pin "5") (pinfunction "S15_5") (pintype "input"))
    )
    (net (code "86") (name "Net-(U8-S16)") (class "Default")
      (node (ref "R43") (pin "2") (pinfunction "2_2") (pintype "passive"))
      (node (ref "U8") (pin "4") (pinfunction "S16_4") (pintype "input"))
    )
    (net (code "87") (name "Net-(U10A-IN+)") (class "Default")
      (node (ref "C29") (pin "1") (pinfunction "1_1") (pintype "passive"))
      (node (ref "R32") (pin "2") (pinfunction "2_2") (pintype "passive"))
      (node (ref "U10") (pin "3") (pinfunction "IN+_3") (pintype "input"))
    )
    (net (code "88") (name "Net-(U10A-IN-)") (class "Default")
      (node (ref "C26") (pin "1") (pinfunction "1_1") (pintype "passive"))
      (node (ref "R35") (pin "1") (pinfunction "1_1") (pintype "passive"))
      (node (ref "U10") (pin "1") (pinfunction "OUT_1") (pintype "output"))
      (node (ref "U10") (pin "2") (pinfunction "IN-_2") (pintype "input"))
    )
    (net (code "89") (name "Net-(U10B-IN+)") (class "Default")
      (node (ref "C30") (pin "1") (pinfunction "1_1") (pintype "passive"))
      (node (ref "R36") (pin "2") (pinfunction "2_2") (pintype "passive"))
      (node (ref "U10") (pin "5") (pinfunction "IN+_5") (pintype "input"))
    )
    (net (code "90") (name "Net-(U10B-IN-)") (class "Default")
      (node (ref "C27") (pin "1") (pinfunction "1_1") (pintype "passive"))
      (node (ref "R38") (pin "1") (pinfunction "1_1") (pintype "passive"))
      (node (ref "U10") (pin "6") (pinfunction "IN-_6") (pintype "input"))
      (node (ref "U10") (pin "7") (pinfunction "OUT_7") (pintype "output"))
    )
    (net (code "91") (name "Net-(U10C-IN+)") (class "Default")
      (node (ref "R38") (pin "2") (pinfunction "2_2") (pintype "passive"))
      (node (ref "R44") (pin "2") (pinfunction "2_2") (pintype "passive"))
      (node (ref "U10") (pin "10") (pinfunction "IN+_10") (pintype "input"))
    )
    (net (code "92") (name "Net-(U10C-IN-)") (class "Default")
      (node (ref "R47") (pin "1") (pinfunction "1_1") (pintype "passive"))
      (node (ref "R48") (pin "1") (pinfunction "1_1") (pintype "passive"))
      (node (ref "U10") (pin "9") (pinfunction "IN-_9") (pintype "input"))
    )
    (net (code "93") (name "Net-(U10C-OUT)") (class "Default")
      (node (ref "R47") (pin "2") (pinfunction "2_2") (pintype "passive"))
      (node (ref "U10") (pin "12") (pinfunction "IN+_12") (pintype "input"))
      (node (ref "U10") (pin "8") (pinfunction "OUT_8") (pintype "output"))
    )
    (net (code "94") (name "Net-(U11-S1)") (class "Default")
      (node (ref "R51") (pin "2") (pinfunction "2_2") (pintype "passive"))
      (node (ref "U11") (pin "19") (pinfunction "S1_19") (pintype "input"))
    )
    (net (code "95") (name "Net-(U11-S2)") (class "Default")
      (node (ref "R52") (pin "2") (pinfunction "2_2") (pintype "passive"))
      (node (ref "U11") (pin "20") (pinfunction "S2_20") (pintype "input"))
    )
    (net (code "96") (name "Net-(U11-S3)") (class "Default")
      (node (ref "R53") (pin "2") (pinfunction "2_2") (pintype "passive"))
      (node (ref "U11") (pin "21") (pinfunction "S3_21") (pintype "input"))
    )
    (net (code "97") (name "Net-(U11-S4)") (class "Default")
      (node (ref "R54") (pin "2") (pinfunction "2_2") (pintype "passive"))
      (node (ref "U11") (pin "22") (pinfunction "S4_22") (pintype "input"))
    )
    (net (code "98") (name "Net-(U11-S5)") (class "Default")
      (node (ref "R55") (pin "2") (pinfunction "2_2") (pintype "passive"))
      (node (ref "U11") (pin "23") (pinfunction "S5_23") (pintype "input"))
    )
    (net (code "99") (name "Net-(U11-S6)") (class "Default")
      (node (ref "R57") (pin "2") (pinfunction "2_2") (pintype "passive"))
      (node (ref "U11") (pin "24") (pinfunction "S6_24") (pintype "input"))
    )
    (net (code "100") (name "Net-(U11-S7)") (class "Default")
      (node (ref "R58") (pin "2") (pinfunction "2_2") (pintype "passive"))
      (node (ref "U11") (pin "25") (pinfunction "S7_25") (pintype "input"))
    )
    (net (code "101") (name "Net-(U11-S8)") (class "Default")
      (node (ref "R59") (pin "2") (pinfunction "2_2") (pintype "passive"))
      (node (ref "U11") (pin "26") (pinfunction "S8_26") (pintype "input"))
    )
    (net (code "102") (name "Net-(U11-S9)") (class "Default")
      (node (ref "R60") (pin "2") (pinfunction "2_2") (pintype "passive"))
      (node (ref "U11") (pin "11") (pinfunction "S9_11") (pintype "input"))
    )
    (net (code "103") (name "Net-(U11-S10)") (class "Default")
      (node (ref "R61") (pin "2") (pinfunction "2_2") (pintype "passive"))
      (node (ref "U11") (pin "10") (pinfunction "S10_10") (pintype "input"))
    )
    (net (code "104") (name "Net-(U11-S11)") (class "Default")
      (node (ref "R64") (pin "2") (pinfunction "2_2") (pintype "passive"))
      (node (ref "U11") (pin "9") (pinfunction "S11_9") (pintype "input"))
    )
    (net (code "105") (name "Net-(U11-S12)") (class "Default")
      (node (ref "R68") (pin "2") (pinfunction "2_2") (pintype "passive"))
      (node (ref "U11") (pin "8") (pinfunction "S12_8") (pintype "input"))
    )
    (net (code "106") (name "Net-(U11-S13)") (class "Default")
      (node (ref "R70") (pin "2") (pinfunction "2_2") (pintype "passive"))
      (node (ref "U11") (pin "7") (pinfunction "S13_7") (pintype "input"))
    )
    (net (code "107") (name "Net-(U11-S14)") (class "Default")
      (node (ref "R71") (pin "2") (pinfunction "2_2") (pintype "passive"))
      (node (ref "U11") (pin "6") (pinfunction "S14_6") (pintype "input"))
    )
    (net (code "108") (name "Net-(U11-S15)") (class "Default")
      (node (ref "R72") (pin "2") (pinfunction "2_2") (pintype "passive"))
      (node (ref "U11") (pin "5") (pinfunction "S15_5") (pintype "input"))
    )
    (net (code "109") (name "Net-(U11-S16)") (class "Default")
      (node (ref "R73") (pin "2") (pinfunction "2_2") (pintype "passive"))
      (node (ref "U11") (pin "4") (pinfunction "S16_4") (pintype "input"))
    )
    (net (code "110") (name "Net-(U13A-IN+)") (class "Default")
      (node (ref "C41") (pin "1") (pinfunction "1_1") (pintype "passive"))
      (node (ref "R63") (pin "2") (pinfunction "2_2") (pintype "passive"))
      (node (ref "U13") (pin "3") (pinfunction "IN+_3") (pintype "input"))
    )
    (net (code "111") (name "Net-(U13A-IN-)") (class "Default")
      (node (ref "C37") (pin "1") (pinfunction "1_1") (pintype "passive"))
      (node (ref "R66") (pin "1") (pinfunction "1_1") (pintype "passive"))
      (node (ref "U13") (pin "1") (pinfunction "OUT_1") (pintype "output"))
      (node (ref "U13") (pin "2") (pinfunction "IN-_2") (pintype "input"))
    )
    (net (code "112") (name "Net-(U13B-IN+)") (class "Default")
      (node (ref "C42") (pin "1") (pinfunction "1_1") (pintype "passive"))
      (node (ref "R67") (pin "2") (pinfunction "2_2") (pintype "passive"))
      (node (ref "U13") (pin "5") (pinfunction "IN+_5") (pintype "input"))
    )
    (net (code "113") (name "Net-(U13B-IN-)") (class "Default")
      (node (ref "C38") (pin "1") (pinfunction "1_1") (pintype "passive"))
      (node (ref "R69") (pin "1") (pinfunction "1_1") (pintype "passive"))
      (node (ref "U13") (pin "6") (pinfunction "IN-_6") (pintype "input"))
      (node (ref "U13") (pin "7") (pinfunction "OUT_7") (pintype "output"))
    )
    (net (code "114") (name "Net-(U13C-IN+)") (class "Default")
      (node (ref "R69") (pin "2") (pinfunction "2_2") (pintype "passive"))
      (node (ref "R74") (pin "2") (pinfunction "2_2") (pintype "passive"))
      (node (ref "U13") (pin "10") (pinfunction "IN+_10") (pintype "input"))
    )
    (net (code "115") (name "Net-(U13C-IN-)") (class "Default")
      (node (ref "R77") (pin "1") (pinfunction "1_1") (pintype "passive"))
      (node (ref "R78") (pin "1") (pinfunction "1_1") (pintype "passive"))
      (node (ref "U13") (pin "9") (pinfunction "IN-_9") (pintype "input"))
    )
    (net (code "116") (name "Net-(U13C-OUT)") (class "Default")
      (node (ref "R77") (pin "2") (pinfunction "2_2") (pintype "passive"))
      (node (ref "U13") (pin "12") (pinfunction "IN+_12") (pintype "input"))
      (node (ref "U13") (pin "8") (pinfunction "OUT_8") (pintype "output"))
    )
    (net (code "117") (name "Net-(U14-X1)") (class "Default")
      (node (ref "U14") (pin "1") (pinfunction "X1_1") (pintype "passive"))
      (node (ref "Y2") (pin "2") (pinfunction "OSC2_2") (pintype "passive"))
    )
    (net (code "118") (name "Net-(U14-X2)") (class "Default")
      (node (ref "U14") (pin "2") (pinfunction "X2_2") (pintype "passive"))
      (node (ref "Y2") (pin "1") (pinfunction "OSC1_1") (pintype "passive"))
    )
    (net (code "119") (name "Net-(U15-S1)") (class "Default")
      (node (ref "R85") (pin "2") (pinfunction "2_2") (pintype "passive"))
      (node (ref "U15") (pin "19") (pinfunction "S1_19") (pintype "input"))
    )
    (net (code "120") (name "Net-(U15-S2)") (class "Default")
      (node (ref "R86") (pin "2") (pinfunction "2_2") (pintype "passive"))
      (node (ref "U15") (pin "20") (pinfunction "S2_20") (pintype "input"))
    )
    (net (code "121") (name "Net-(U15-S3)") (class "Default")
      (node (ref "R87") (pin "2") (pinfunction "2_2") (pintype "passive"))
      (node (ref "U15") (pin "21") (pinfunction "S3_21") (pintype "input"))
    )
    (net (code "122") (name "Net-(U15-S4)") (class "Default")
      (node (ref "R88") (pin "2") (pinfunction "2_2") (pintype "passive"))
      (node (ref "U15") (pin "22") (pinfunction "S4_22") (pintype "input"))
    )
    (net (code "123") (name "Net-(U15-S5)") (class "Default")
      (node (ref "R89") (pin "2") (pinfunction "2_2") (pintype "passive"))
      (node (ref "U15") (pin "23") (pinfunction "S5_23") (pintype "input"))
    )
    (net (code "124") (name "Net-(U15-S6)") (class "Default")
      (node (ref "R91") (pin "2") (pinfunction "2_2") (pintype "passive"))
      (node (ref "U15") (pin "24") (pinfunction "S6_24") (pintype "input"))
    )
    (net (code "125") (name "Net-(U15-S7)") (class "Default")
      (node (ref "R92") (pin "2") (pinfunction "2_2") (pintype "passive"))
      (node (ref "U15") (pin "25") (pinfunction "S7_25") (pintype "input"))
    )
    (net (code "126") (name "Net-(U15-S8)") (class "Default")
      (node (ref "R93") (pin "2") (pinfunction "2_2") (pintype "passive"))
      (node (ref "U15") (pin "26") (pinfunction "S8_26") (pintype "input"))
    )
    (net (code "127") (name "Net-(U15-S9)") (class "Default")
      (node (ref "R98") (pin "2") (pinfunction "2_2") (pintype "passive"))
      (node (ref "U15") (pin "11") (pinfunction "S9_11") (pintype "input"))
    )
    (net (code "128") (name "Net-(U15-S10)") (class "Default")
      (node (ref "R99") (pin "2") (pinfunction "2_2") (pintype "passive"))
      (node (ref "U15") (pin "10") (pinfunction "S10_10") (pintype "input"))
    )
    (net (code "129") (name "Net-(U15-S11)") (class "Default")
      (node (ref "R102") (pin "2") (pinfunction "2_2") (pintype "passive"))
      (node (ref "U15") (pin "9") (pinfunction "S11_9") (pintype "input"))
    )
    (net (code "130") (name "Net-(U15-S12)") (class "Default")
      (node (ref "R106") (pin "2") (pinfunction "2_2") (pintype "passive"))
      (node (ref "U15") (pin "8") (pinfunction "S12_8") (pintype "input"))
    )
    (net (code "131") (name "Net-(U15-S13)") (class "Default")
      (node (ref "R108") (pin "2") (pinfunction "2_2") (pintype "passive"))
      (node (ref "U15") (pin "7") (pinfunction "S13_7") (pintype "input"))
    )
    (net (code "132") (name "Net-(U15-S14)") (class "Default")
      (node (ref "R109") (pin "2") (pinfunction "2_2") (pintype "passive"))
      (node (ref "U15") (pin "6") (pinfunction "S14_6") (pintype "input"))
    )
    (net (code "133") (name "Net-(U15-S15)") (class "Default")
      (node (ref "R110") (pin "2") (pinfunction "2_2") (pintype "passive"))
      (node (ref "U15") (pin "5") (pinfunction "S15_5") (pintype "input"))
    )
    (net (code "134") (name "Net-(U15-S16)") (class "Default")
      (node (ref "R111") (pin "2") (pinfunction "2_2") (pintype "passive"))
      (node (ref "U15") (pin "4") (pinfunction "S16_4") (pintype "input"))
    )
    (net (code "135") (name "Net-(U17A-IN+)") (class "Default")
      (node (ref "C55") (pin "1") (pinfunction "1_1") (pintype "passive"))
      (node (ref "R101") (pin "2") (pinfunction "2_2") (pintype "passive"))
      (node (ref "U17") (pin "3") (pinfunction "IN+_3") (pintype "input"))
    )
    (net (code "136") (name "Net-(U17A-IN-)") (class "Default")
      (node (ref "C52") (pin "1") (pinfunction "1_1") (pintype "passive"))
      (node (ref "R104") (pin "1") (pinfunction "1_1") (pintype "passive"))
      (node (ref "U17") (pin "1") (pinfunction "OUT_1") (pintype "output"))
      (node (ref "U17") (pin "2") (pinfunction "IN-_2") (pintype "input"))
    )
    (net (code "137") (name "Net-(U17B-IN+)") (class "Default")
      (node (ref "C56") (pin "1") (pinfunction "1_1") (pintype "passive"))
      (node (ref "R105") (pin "2") (pinfunction "2_2") (pintype "passive"))
      (node (ref "U17") (pin "5") (pinfunction "IN+_5") (pintype "input"))
    )
    (net (code "138") (name "Net-(U17B-IN-)") (class "Default")
      (node (ref "C53") (pin "1") (pinfunction "1_1") (pintype "passive"))
      (node (ref "R107") (pin "1") (pinfunction "1_1") (pintype "passive"))
      (node (ref "U17") (pin "6") (pinfunction "IN-_6") (pintype "input"))
      (node (ref "U17") (pin "7") (pinfunction "OUT_7") (pintype "output"))
    )
    (net (code "139") (name "Net-(U17C-IN+)") (class "Default")
      (node (ref "R107") (pin "2") (pinfunction "2_2") (pintype "passive"))
      (node (ref "R112") (pin "2") (pinfunction "2_2") (pintype "passive"))
      (node (ref "U17") (pin "10") (pinfunction "IN+_10") (pintype "input"))
    )
    (net (code "140") (name "Net-(U17C-IN-)") (class "Default")
      (node (ref "R115") (pin "1") (pinfunction "1_1") (pintype "passive"))
      (node (ref "R116") (pin "1") (pinfunction "1_1") (pintype "passive"))
      (node (ref "U17") (pin "9") (pinfunction "IN-_9") (pintype "input"))
    )
    (net (code "141") (name "Net-(U17C-OUT)") (class "Default")
      (node (ref "R115") (pin "2") (pinfunction "2_2") (pintype "passive"))
      (node (ref "U17") (pin "12") (pinfunction "IN+_12") (pintype "input"))
      (node (ref "U17") (pin "8") (pinfunction "OUT_8") (pintype "output"))
    )
    (net (code "142") (name "PGC") (class "Default")
      (node (ref "P9") (pin "5") (pinfunction "5_5") (pintype "passive"))
      (node (ref "R2") (pin "2") (pinfunction "2_2") (pintype "passive"))
      (node (ref "U4") (pin "8") (pinfunction "PGC/EMUC/AN6/OCFA/RB6_8") (pintype "bidirectional"))
    )
    (net (code "143") (name "PGD") (class "Default")
      (node (ref "P9") (pin "4") (pinfunction "4_4") (pintype "passive"))
      (node (ref "U4") (pin "9") (pinfunction "PGD/EMUD/AN7/RB7_9") (pintype "bidirectional"))
    )
    (net (code "144") (name "PIN_EXTRA_3.3V") (class "Default")
      (node (ref "P12") (pin "40") (pinfunction "40_40") (pintype "passive"))
      (node (ref "Q7") (pin "2") (pinfunction "S_2") (pintype "passive"))
      (node (ref "R120") (pin "1") (pinfunction "1_1") (pintype "passive"))
    )
    (net (code "145") (name "PIN_EXTRA_5V") (class "Default")
      (node (ref "Q7") (pin "3") (pinfunction "D_3") (pintype "passive"))
      (node (ref "R121") (pin "1") (pinfunction "1_1") (pintype "passive"))
      (node (ref "U4") (pin "33") (pinfunction "EMUD2/OC2/RD1_33") (pintype "bidirectional"))
    )
    (net (code "146") (name "PIN_PIC_LIBRE") (class "Default")
      (node (ref "P2") (pin "5") (pinfunction "5_5") (pintype "passive"))
      (node (ref "U4") (pin "3") (pinfunction "AN1/VREF-/CN3/RB1_3") (pintype "bidirectional"))
    )
    (net (code "147") (name "PIN_RPi_LIBRE_1") (class "Default")
      (node (ref "P11") (pin "3") (pinfunction "3_3") (pintype "passive"))
      (node (ref "P12") (pin "3") (pinfunction "3_3") (pintype "passive"))
    )
    (net (code "148") (name "PIN_RPi_LIBRE_2") (class "Default")
      (node (ref "P11") (pin "4") (pinfunction "4_4") (pintype "passive"))
      (node (ref "P12") (pin "5") (pinfunction "5_5") (pintype "passive"))
    )
    (net (code "149") (name "PIN_RPi_LIBRE_3") (class "Default")
      (node (ref "P11") (pin "5") (pinfunction "5_5") (pintype "passive"))
      (node (ref "P12") (pin "8") (pinfunction "8_8") (pintype "passive"))
    )
    (net (code "150") (name "PIN_RPi_LIBRE_4") (class "Default")
      (node (ref "P11") (pin "6") (pinfunction "6_6") (pintype "passive"))
      (node (ref "P12") (pin "10") (pinfunction "10_10") (pintype "passive"))
    )
    (net (code "151") (name "PPS_GPS") (class "Default")
      (node (ref "GPS1") (pin "0") (pinfunction "1PPS_0") (pintype "passive"))
      (node (ref "R119") (pin "2") (pinfunction "2_2") (pintype "passive"))
      (node (ref "U4") (pin "17") (pinfunction "INT0/RA11_17") (pintype "bidirectional"))
    )
    (net (code "152") (name "RES1") (class "Default")
      (node (ref "U8") (pin "28") (pinfunction "D_28") (pintype "output"))
      (node (ref "U9") (pin "1") (pinfunction "1_1") (pintype "passive"))
    )
    (net (code "153") (name "RES1B") (class "Default")
      (node (ref "R20") (pin "1") (pinfunction "1_1") (pintype "passive"))
      (node (ref "R21") (pin "1") (pinfunction "1_1") (pintype "passive"))
      (node (ref "R22") (pin "1") (pinfunction "1_1") (pintype "passive"))
      (node (ref "R24") (pin "1") (pinfunction "1_1") (pintype "passive"))
      (node (ref "R25") (pin "1") (pinfunction "1_1") (pintype "passive"))
      (node (ref "R27") (pin "1") (pinfunction "1_1") (pintype "passive"))
      (node (ref "R28") (pin "1") (pinfunction "1_1") (pintype "passive"))
      (node (ref "R29") (pin "1") (pinfunction "1_1") (pintype "passive"))
      (node (ref "R30") (pin "1") (pinfunction "1_1") (pintype "passive"))
      (node (ref "R34") (pin "1") (pinfunction "1_1") (pintype "passive"))
      (node (ref "R37") (pin "1") (pinfunction "1_1") (pintype "passive"))
      (node (ref "R39") (pin "1") (pinfunction "1_1") (pintype "passive"))
      (node (ref "R40") (pin "1") (pinfunction "1_1") (pintype "passive"))
      (node (ref "R41") (pin "1") (pinfunction "1_1") (pintype "passive"))
      (node (ref "R42") (pin "1") (pinfunction "1_1") (pintype "passive"))
      (node (ref "R43") (pin "1") (pinfunction "1_1") (pintype "passive"))
      (node (ref "U9") (pin "8") (pinfunction "8_8") (pintype "passive"))
    )
    (net (code "154") (name "RES2") (class "Default")
      (node (ref "U11") (pin "28") (pinfunction "D_28") (pintype "output"))
      (node (ref "U12") (pin "1") (pinfunction "1_1") (pintype "passive"))
    )
    (net (code "155") (name "RES2B") (class "Default")
      (node (ref "R51") (pin "1") (pinfunction "1_1") (pintype "passive"))
      (node (ref "R52") (pin "1") (pinfunction "1_1") (pintype "passive"))
      (node (ref "R53") (pin "1") (pinfunction "1_1") (pintype "passive"))
      (node (ref "R54") (pin "1") (pinfunction "1_1") (pintype "passive"))
      (node (ref "R55") (pin "1") (pinfunction "1_1") (pintype "passive"))
      (node (ref "R57") (pin "1") (pinfunction "1_1") (pintype "passive"))
      (node (ref "R58") (pin "1") (pinfunction "1_1") (pintype "passive"))
      (node (ref "R59") (pin "1") (pinfunction "1_1") (pintype "passive"))
      (node (ref "R60") (pin "1") (pinfunction "1_1") (pintype "passive"))
      (node (ref "R61") (pin "1") (pinfunction "1_1") (pintype "passive"))
      (node (ref "R64") (pin "1") (pinfunction "1_1") (pintype "passive"))
      (node (ref "R68") (pin "1") (pinfunction "1_1") (pintype "passive"))
      (node (ref "R70") (pin "1") (pinfunction "1_1") (pintype "passive"))
      (node (ref "R71") (pin "1") (pinfunction "1_1") (pintype "passive"))
      (node (ref "R72") (pin "1") (pinfunction "1_1") (pintype "passive"))
      (node (ref "R73") (pin "1") (pinfunction "1_1") (pintype "passive"))
      (node (ref "U12") (pin "8") (pinfunction "8_8") (pintype "passive"))
    )
    (net (code "156") (name "RES3") (class "Default")
      (node (ref "U15") (pin "28") (pinfunction "D_28") (pintype "output"))
      (node (ref "U16") (pin "1") (pinfunction "1_1") (pintype "passive"))
    )
    (net (code "157") (name "RES3B") (class "Default")
      (node (ref "R102") (pin "1") (pinfunction "1_1") (pintype "passive"))
      (node (ref "R106") (pin "1") (pinfunction "1_1") (pintype "passive"))
      (node (ref "R108") (pin "1") (pinfunction "1_1") (pintype "passive"))
      (node (ref "R109") (pin "1") (pinfunction "1_1") (pintype "passive"))
      (node (ref "R110") (pin "1") (pinfunction "1_1") (pintype "passive"))
      (node (ref "R111") (pin "1") (pinfunction "1_1") (pintype "passive"))
      (node (ref "R85") (pin "1") (pinfunction "1_1") (pintype "passive"))
      (node (ref "R86") (pin "1") (pinfunction "1_1") (pintype "passive"))
      (node (ref "R87") (pin "1") (pinfunction "1_1") (pintype "passive"))
      (node (ref "R88") (pin "1") (pinfunction "1_1") (pintype "passive"))
      (node (ref "R89") (pin "1") (pinfunction "1_1") (pintype "passive"))
      (node (ref "R91") (pin "1") (pinfunction "1_1") (pintype "passive"))
      (node (ref "R92") (pin "1") (pinfunction "1_1") (pintype "passive"))
      (node (ref "R93") (pin "1") (pinfunction "1_1") (pintype "passive"))
      (node (ref "R98") (pin "1") (pinfunction "1_1") (pintype "passive"))
      (node (ref "R99") (pin "1") (pinfunction "1_1") (pintype "passive"))
      (node (ref "U16") (pin "8") (pinfunction "8_8") (pintype "passive"))
    )
    (net (code "158") (name "RESET_RPi") (class "Default")
      (node (ref "Q1") (pin "2") (pinfunction "G_2") (pintype "passive"))
      (node (ref "R26") (pin "2") (pinfunction "2_2") (pintype "passive"))
      (node (ref "U4") (pin "30") (pinfunction "RF0_30") (pintype "bidirectional"))
    )
    (net (code "159") (name "RESET_dsPIC_3.3V") (class "Default")
      (node (ref "P12") (pin "38") (pinfunction "38_38") (pintype "passive"))
      (node (ref "Q6") (pin "2") (pinfunction "S_2") (pintype "passive"))
      (node (ref "R96") (pin "1") (pinfunction "1_1") (pintype "passive"))
    )
    (net (code "160") (name "RESET_dsPIC_5V") (class "Default")
      (node (ref "P10") (pin "1") (pinfunction "1_1") (pintype "passive"))
      (node (ref "Q6") (pin "3") (pinfunction "D_3") (pintype "passive"))
      (node (ref "R97") (pin "1") (pinfunction "1_1") (pintype "passive"))
    )
    (net (code "161") (name "RX_GPS") (class "Default")
      (node (ref "GPS1") (pin "3") (pinfunction ">RX_3") (pintype "passive"))
      (node (ref "U4") (pin "15") (pinfunction "EMUD1/SOSCI/T2CK/U1ATX/CN1/RC13_15") (pintype "bidirectional"))
    )
    (net (code "162") (name "Referencia") (class "Default")
      (node (ref "R112") (pin "1") (pinfunction "1_1") (pintype "passive"))
      (node (ref "R44") (pin "1") (pinfunction "1_1") (pintype "passive"))
      (node (ref "R74") (pin "1") (pinfunction "1_1") (pintype "passive"))
      (node (ref "U4") (pin "35") (pinfunction "AN12/RB12_35") (pintype "bidirectional"))
      (node (ref "U7") (pin "1") (pinfunction "OUT_1") (pintype "output"))
      (node (ref "U7") (pin "2") (pinfunction "IN-_2") (pintype "input"))
    )
    (net (code "163") (name "SCK_3.3V") (class "Default")
      (node (ref "P12") (pin "23") (pinfunction "23_23") (pintype "passive"))
      (node (ref "Q5") (pin "2") (pinfunction "S_2") (pintype "passive"))
      (node (ref "R94") (pin "1") (pinfunction "1_1") (pintype "passive"))
    )
    (net (code "164") (name "SCK_5V") (class "Default")
      (node (ref "Q5") (pin "3") (pinfunction "D_3") (pintype "passive"))
      (node (ref "R95") (pin "1") (pinfunction "1_1") (pintype "passive"))
      (node (ref "U4") (pin "24") (pinfunction "EMUC3/SCK1/RF6_24") (pintype "bidirectional"))
    )
    (net (code "165") (name "SCL_DS1307") (class "Default")
      (node (ref "R79") (pin "2") (pinfunction "2_2") (pintype "passive"))
      (node (ref "U14") (pin "6") (pinfunction "SCL_6") (pintype "bidirectional"))
      (node (ref "U4") (pin "22") (pinfunction "RD2_22") (pintype "bidirectional"))
    )
    (net (code "166") (name "SDA_DS1307") (class "Default")
      (node (ref "R80") (pin "2") (pinfunction "2_2") (pintype "passive"))
      (node (ref "U14") (pin "5") (pinfunction "SDA_5") (pintype "bidirectional"))
      (node (ref "U4") (pin "23") (pinfunction "IC1/INT1/RD8_23") (pintype "bidirectional"))
    )
    (net (code "167") (name "Señal1") (class "Default")
      (node (ref "U10") (pin "13") (pinfunction "IN-_13") (pintype "input"))
      (node (ref "U10") (pin "14") (pinfunction "OUT_14") (pintype "output"))
      (node (ref "U4") (pin "36") (pinfunction "AN11/RB11_36") (pintype "bidirectional"))
    )
    (net (code "168") (name "Señal2") (class "Default")
      (node (ref "U13") (pin "13") (pinfunction "IN-_13") (pintype "input"))
      (node (ref "U13") (pin "14") (pinfunction "OUT_14") (pintype "output"))
      (node (ref "U4") (pin "37") (pinfunction "AN10/RB10_37") (pintype "bidirectional"))
    )
    (net (code "169") (name "Señal3") (class "Default")
      (node (ref "U17") (pin "13") (pinfunction "IN-_13") (pintype "input"))
      (node (ref "U17") (pin "14") (pinfunction "OUT_14") (pintype "output"))
      (node (ref "U4") (pin "38") (pinfunction "AN9/RB9_38") (pintype "bidirectional"))
    )
    (net (code "170") (name "TX_GPS_3.3V") (class "Default")
      (node (ref "GPS1") (pin "4") (pinfunction "<TX_4") (pintype "passive"))
      (node (ref "Q2") (pin "2") (pinfunction "S_2") (pintype "passive"))
      (node (ref "R49") (pin "1") (pinfunction "1_1") (pintype "passive"))
    )
    (net (code "171") (name "TX_GPS_5V") (class "Default")
      (node (ref "Q2") (pin "3") (pinfunction "D_3") (pintype "passive"))
      (node (ref "R50") (pin "1") (pinfunction "1_1") (pintype "passive"))
      (node (ref "U4") (pin "16") (pinfunction "EMUC1/SOSCO/T1CK/U1ARX/CN0/RC14_16") (pintype "bidirectional"))
    )
    (net (code "172") (name "U2RX") (class "Default")
      (node (ref "P2") (pin "3") (pinfunction "3_3") (pintype "passive"))
      (node (ref "U4") (pin "28") (pinfunction "U2RX/CN17/RF4_28") (pintype "bidirectional"))
    )
    (net (code "173") (name "U2TX") (class "Default")
      (node (ref "P2") (pin "4") (pinfunction "4_4") (pintype "passive"))
      (node (ref "U4") (pin "27") (pinfunction "U2TX/CN18/RF5_27") (pintype "bidirectional"))
    )
    (net (code "174") (name "unconnected-(GPS1-3.3V-Pad8)") (class "Default")
      (node (ref "GPS1") (pin "8") (pinfunction "3.3V_8") (pintype "passive"))
    )
    (net (code "175") (name "unconnected-(GPS1-FIX-Pad5)") (class "Default")
      (node (ref "GPS1") (pin "5") (pinfunction "FIX_5") (pintype "passive"))
    )
    (net (code "176") (name "unconnected-(GPS1-VBAT-Pad6)") (class "Default")
      (node (ref "GPS1") (pin "6") (pinfunction "VBAT_6") (pintype "passive"))
    )
    (net (code "177") (name "unconnected-(P3-Pad1)") (class "Default")
      (node (ref "P3") (pin "1") (pinfunction "1_1") (pintype "passive"))
    )
    (net (code "178") (name "unconnected-(P4-Pad1)") (class "Default")
      (node (ref "P4") (pin "1") (pinfunction "1_1") (pintype "passive"))
    )
    (net (code "179") (name "unconnected-(P8-Pad3)") (class "Default")
      (node (ref "P8") (pin "3") (pinfunction "3_3") (pintype "passive"))
    )
    (net (code "180") (name "unconnected-(P9-Pad6)") (class "Default")
      (node (ref "P9") (pin "6") (pinfunction "6_6") (pintype "passive"))
    )
    (net (code "181") (name "unconnected-(P10-Pad3)") (class "Default")
      (node (ref "P10") (pin "3") (pinfunction "3_3") (pintype "passive"))
    )
    (net (code "182") (name "unconnected-(P12-Pad7)") (class "Default")
      (node (ref "P12") (pin "7") (pinfunction "7_7") (pintype "passive"))
    )
    (net (code "183") (name "unconnected-(P12-Pad12)") (class "Default")
      (node (ref "P12") (pin "12") (pinfunction "12_12") (pintype "passive"))
    )
    (net (code "184") (name "unconnected-(P12-Pad13)") (class "Default")
      (node (ref "P12") (pin "13") (pinfunction "13_13") (pintype "passive"))
    )
    (net (code "185") (name "unconnected-(P12-Pad15)") (class "Default")
      (node (ref "P12") (pin "15") (pinfunction "15_15") (pintype "passive"))
    )
    (net (code "186") (name "unconnected-(P12-Pad16)") (class "Default")
      (node (ref "P12") (pin "16") (pinfunction "16_16") (pintype "passive"))
    )
    (net (code "187") (name "unconnected-(P12-Pad18)") (class "Default")
      (node (ref "P12") (pin "18") (pinfunction "18_18") (pintype "passive"))
    )
    (net (code "188") (name "unconnected-(P12-Pad22)") (class "Default")
      (node (ref "P12") (pin "22") (pinfunction "22_22") (pintype "passive"))
    )
    (net (code "189") (name "unconnected-(P12-Pad26)") (class "Default")
      (node (ref "P12") (pin "26") (pinfunction "26_26") (pintype "passive"))
    )
    (net (code "190") (name "unconnected-(P12-Pad27)") (class "Default")
      (node (ref "P12") (pin "27") (pinfunction "27_27") (pintype "passive"))
    )
    (net (code "191") (name "unconnected-(P12-Pad28)") (class "Default")
      (node (ref "P12") (pin "28") (pinfunction "28_28") (pintype "passive"))
    )
    (net (code "192") (name "unconnected-(P12-Pad29)") (class "Default")
      (node (ref "P12") (pin "29") (pinfunction "29_29") (pintype "passive"))
    )
    (net (code "193") (name "unconnected-(P12-Pad31)") (class "Default")
      (node (ref "P12") (pin "31") (pinfunction "31_31") (pintype "passive"))
    )
    (net (code "194") (name "unconnected-(P12-Pad33)") (class "Default")
      (node (ref "P12") (pin "33") (pinfunction "33_33") (pintype "passive"))
    )
    (net (code "195") (name "unconnected-(P12-Pad35)") (class "Default")
      (node (ref "P12") (pin "35") (pinfunction "35_35") (pintype "passive"))
    )
    (net (code "196") (name "unconnected-(P12-Pad37)") (class "Default")
      (node (ref "P12") (pin "37") (pinfunction "37_37") (pintype "passive"))
    )
    (net (code "197") (name "unconnected-(R8-BOT-Pad2)") (class "Default")
      (node (ref "R8") (pin "2") (pinfunction "BOT_2") (pintype "passive"))
    )
    (net (code "198") (name "unconnected-(R9-BOT-Pad2)") (class "Default")
      (node (ref "R9") (pin "2") (pinfunction "BOT_2") (pintype "passive"))
    )
    (net (code "199") (name "unconnected-(U2-NC-Pad1)") (class "Default")
      (node (ref "U2") (pin "1") (pinfunction "NC_1") (pintype "passive"))
    )
    (net (code "200") (name "unconnected-(U2-NC-Pad6)") (class "Default")
      (node (ref "U2") (pin "6") (pinfunction "NC_6") (pintype "passive"))
    )
    (net (code "201") (name "unconnected-(U2-OSC-Pad7)") (class "Default")
      (node (ref "U2") (pin "7") (pinfunction "OSC_7") (pintype "input"))
    )
    (net (code "202") (name "unconnected-(U3-NC-Pad1)") (class "Default")
      (node (ref "U3") (pin "1") (pinfunction "NC_1") (pintype "passive"))
    )
    (net (code "203") (name "unconnected-(U3-NC-Pad6)") (class "Default")
      (node (ref "U3") (pin "6") (pinfunction "NC_6") (pintype "passive"))
    )
    (net (code "204") (name "unconnected-(U3-OSC-Pad7)") (class "Default")
      (node (ref "U3") (pin "7") (pinfunction "OSC_7") (pintype "input"))
    )
    (net (code "205") (name "unconnected-(U4-AN8{slash}RB8-Pad10)") (class "Default")
      (node (ref "U4") (pin "10") (pinfunction "AN8/RB8_10") (pintype "bidirectional"))
    )
    (net (code "206") (name "unconnected-(U8-NC-Pad2)") (class "Default")
      (node (ref "U8") (pin "2") (pinfunction "NC_2") (pintype "passive"))
    )
    (net (code "207") (name "unconnected-(U8-NC-Pad3)") (class "Default")
      (node (ref "U8") (pin "3") (pinfunction "NC_3") (pintype "passive"))
    )
    (net (code "208") (name "unconnected-(U8-NC-Pad13)") (class "Default")
      (node (ref "U8") (pin "13") (pinfunction "NC_13") (pintype "passive"))
    )
    (net (code "209") (name "unconnected-(U10B-V+-Pad4)") (class "Default")
      (node (ref "U10") (pin "4") (pinfunction "V+_4") (pintype "power_in"))
    )
    (net (code "210") (name "unconnected-(U10B-V--Pad11)") (class "Default")
      (node (ref "U10") (pin "11") (pinfunction "V-_11") (pintype "power_in"))
    )
    (net (code "211") (name "unconnected-(U10C-V+-Pad4)") (class "Default")
      (node (ref "U10") (pin "4") (pinfunction "V+_4") (pintype "power_in"))
    )
    (net (code "212") (name "unconnected-(U10C-V--Pad11)") (class "Default")
      (node (ref "U10") (pin "11") (pinfunction "V-_11") (pintype "power_in"))
    )
    (net (code "213") (name "unconnected-(U10D-V+-Pad4)") (class "Default")
      (node (ref "U10") (pin "4") (pinfunction "V+_4") (pintype "power_in"))
    )
    (net (code "214") (name "unconnected-(U10D-V--Pad11)") (class "Default")
      (node (ref "U10") (pin "11") (pinfunction "V-_11") (pintype "power_in"))
    )
    (net (code "215") (name "unconnected-(U11-NC-Pad2)") (class "Default")
      (node (ref "U11") (pin "2") (pinfunction "NC_2") (pintype "passive"))
    )
    (net (code "216") (name "unconnected-(U11-NC-Pad3)") (class "Default")
      (node (ref "U11") (pin "3") (pinfunction "NC_3") (pintype "passive"))
    )
    (net (code "217") (name "unconnected-(U11-NC-Pad13)") (class "Default")
      (node (ref "U11") (pin "13") (pinfunction "NC_13") (pintype "passive"))
    )
    (net (code "218") (name "unconnected-(U13B-V+-Pad4)") (class "Default")
      (node (ref "U13") (pin "4") (pinfunction "V+_4") (pintype "power_in"))
    )
    (net (code "219") (name "unconnected-(U13B-V--Pad11)") (class "Default")
      (node (ref "U13") (pin "11") (pinfunction "V-_11") (pintype "power_in"))
    )
    (net (code "220") (name "unconnected-(U13C-V+-Pad4)") (class "Default")
      (node (ref "U13") (pin "4") (pinfunction "V+_4") (pintype "power_in"))
    )
    (net (code "221") (name "unconnected-(U13C-V--Pad11)") (class "Default")
      (node (ref "U13") (pin "11") (pinfunction "V-_11") (pintype "power_in"))
    )
    (net (code "222") (name "unconnected-(U13D-V+-Pad4)") (class "Default")
      (node (ref "U13") (pin "4") (pinfunction "V+_4") (pintype "power_in"))
    )
    (net (code "223") (name "unconnected-(U13D-V--Pad11)") (class "Default")
      (node (ref "U13") (pin "11") (pinfunction "V-_11") (pintype "power_in"))
    )
    (net (code "224") (name "unconnected-(U15-NC-Pad2)") (class "Default")
      (node (ref "U15") (pin "2") (pinfunction "NC_2") (pintype "passive"))
    )
    (net (code "225") (name "unconnected-(U15-NC-Pad3)") (class "Default")
      (node (ref "U15") (pin "3") (pinfunction "NC_3") (pintype "passive"))
    )
    (net (code "226") (name "unconnected-(U15-NC-Pad13)") (class "Default")
      (node (ref "U15") (pin "13") (pinfunction "NC_13") (pintype "passive"))
    )
    (net (code "227") (name "unconnected-(U17B-V+-Pad4)") (class "Default")
      (node (ref "U17") (pin "4") (pinfunction "V+_4") (pintype "power_in"))
    )
    (net (code "228") (name "unconnected-(U17B-V--Pad11)") (class "Default")
      (node (ref "U17") (pin "11") (pinfunction "V-_11") (pintype "power_in"))
    )
    (net (code "229") (name "unconnected-(U17C-V+-Pad4)") (class "Default")
      (node (ref "U17") (pin "4") (pinfunction "V+_4") (pintype "power_in"))
    )
    (net (code "230") (name "unconnected-(U17C-V--Pad11)") (class "Default")
      (node (ref "U17") (pin "11") (pinfunction "V-_11") (pintype "power_in"))
    )
    (net (code "231") (name "unconnected-(U17D-V+-Pad4)") (class "Default")
      (node (ref "U17") (pin "4") (pinfunction "V+_4") (pintype "power_in"))
    )
    (net (code "232") (name "unconnected-(U17D-V--Pad11)") (class "Default")
      (node (ref "U17") (pin "11") (pinfunction "V-_11") (pintype "power_in"))
    )
  )
)
